# io-board-d-8.net
KiCad netlist of a schematic drawn in EAGLE
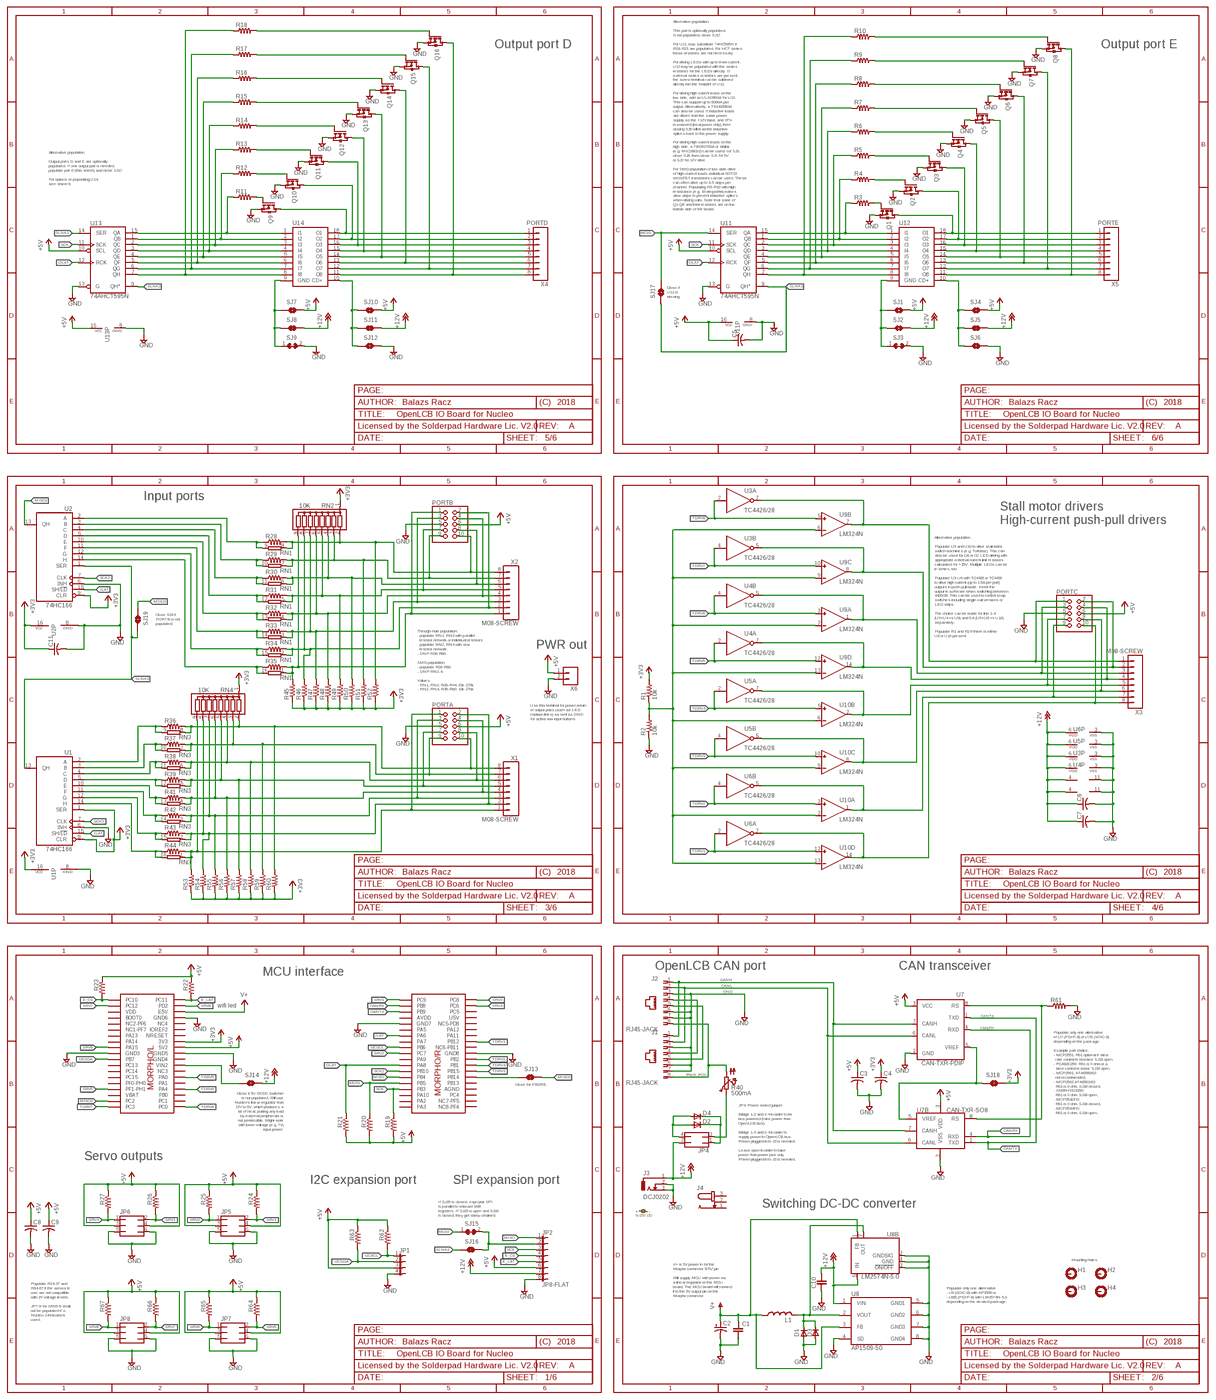
[diagram p0: schematic, sheet 1, overview]
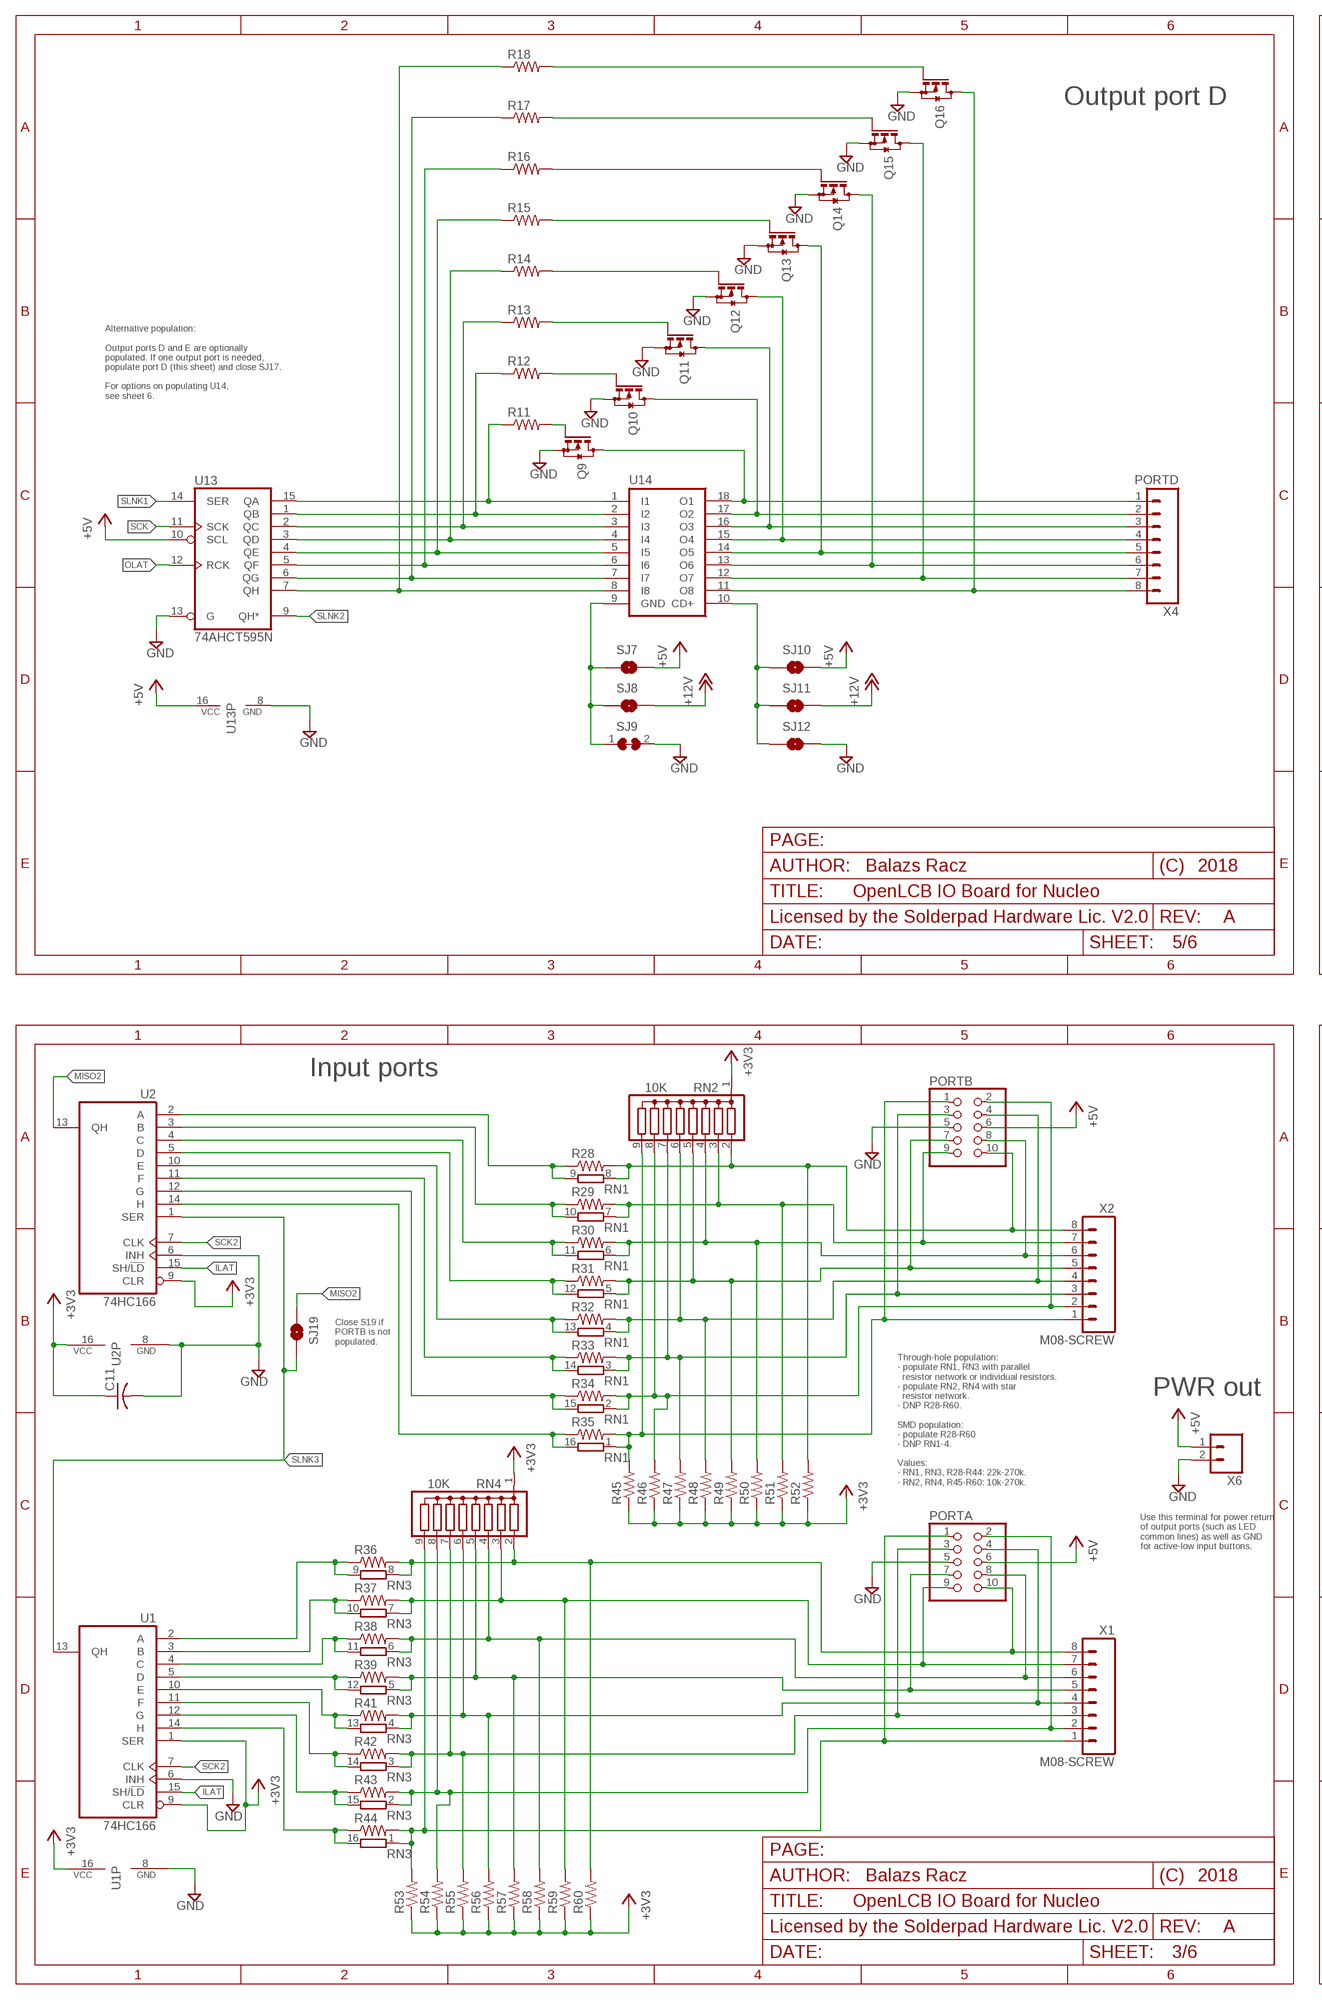
[diagram p1: schematic, sheet 1, part 1 of 4]
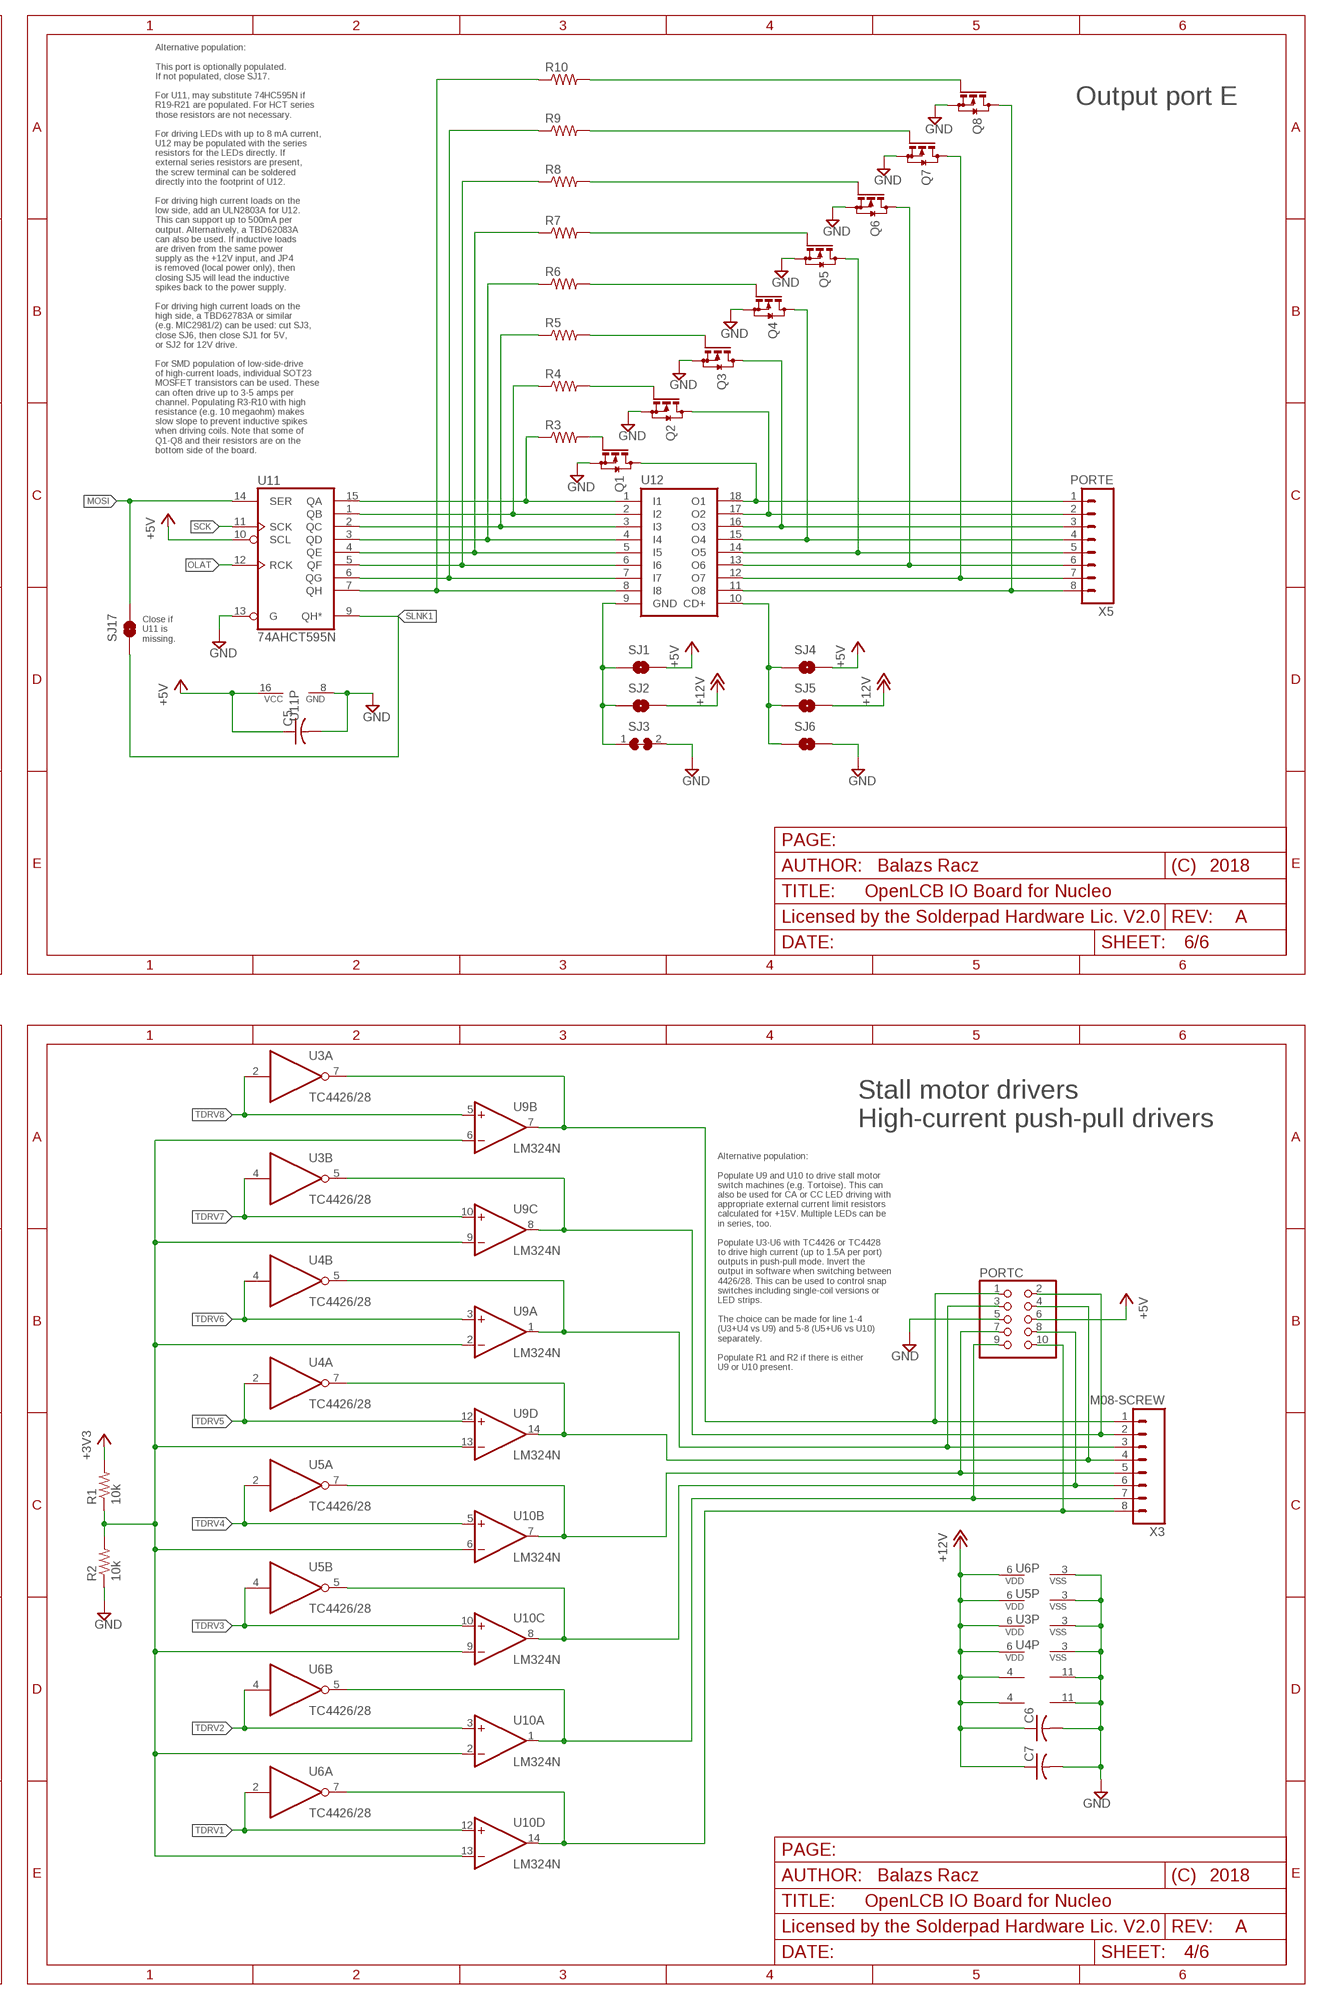
[diagram p2: schematic, sheet 1, part 2 of 4]
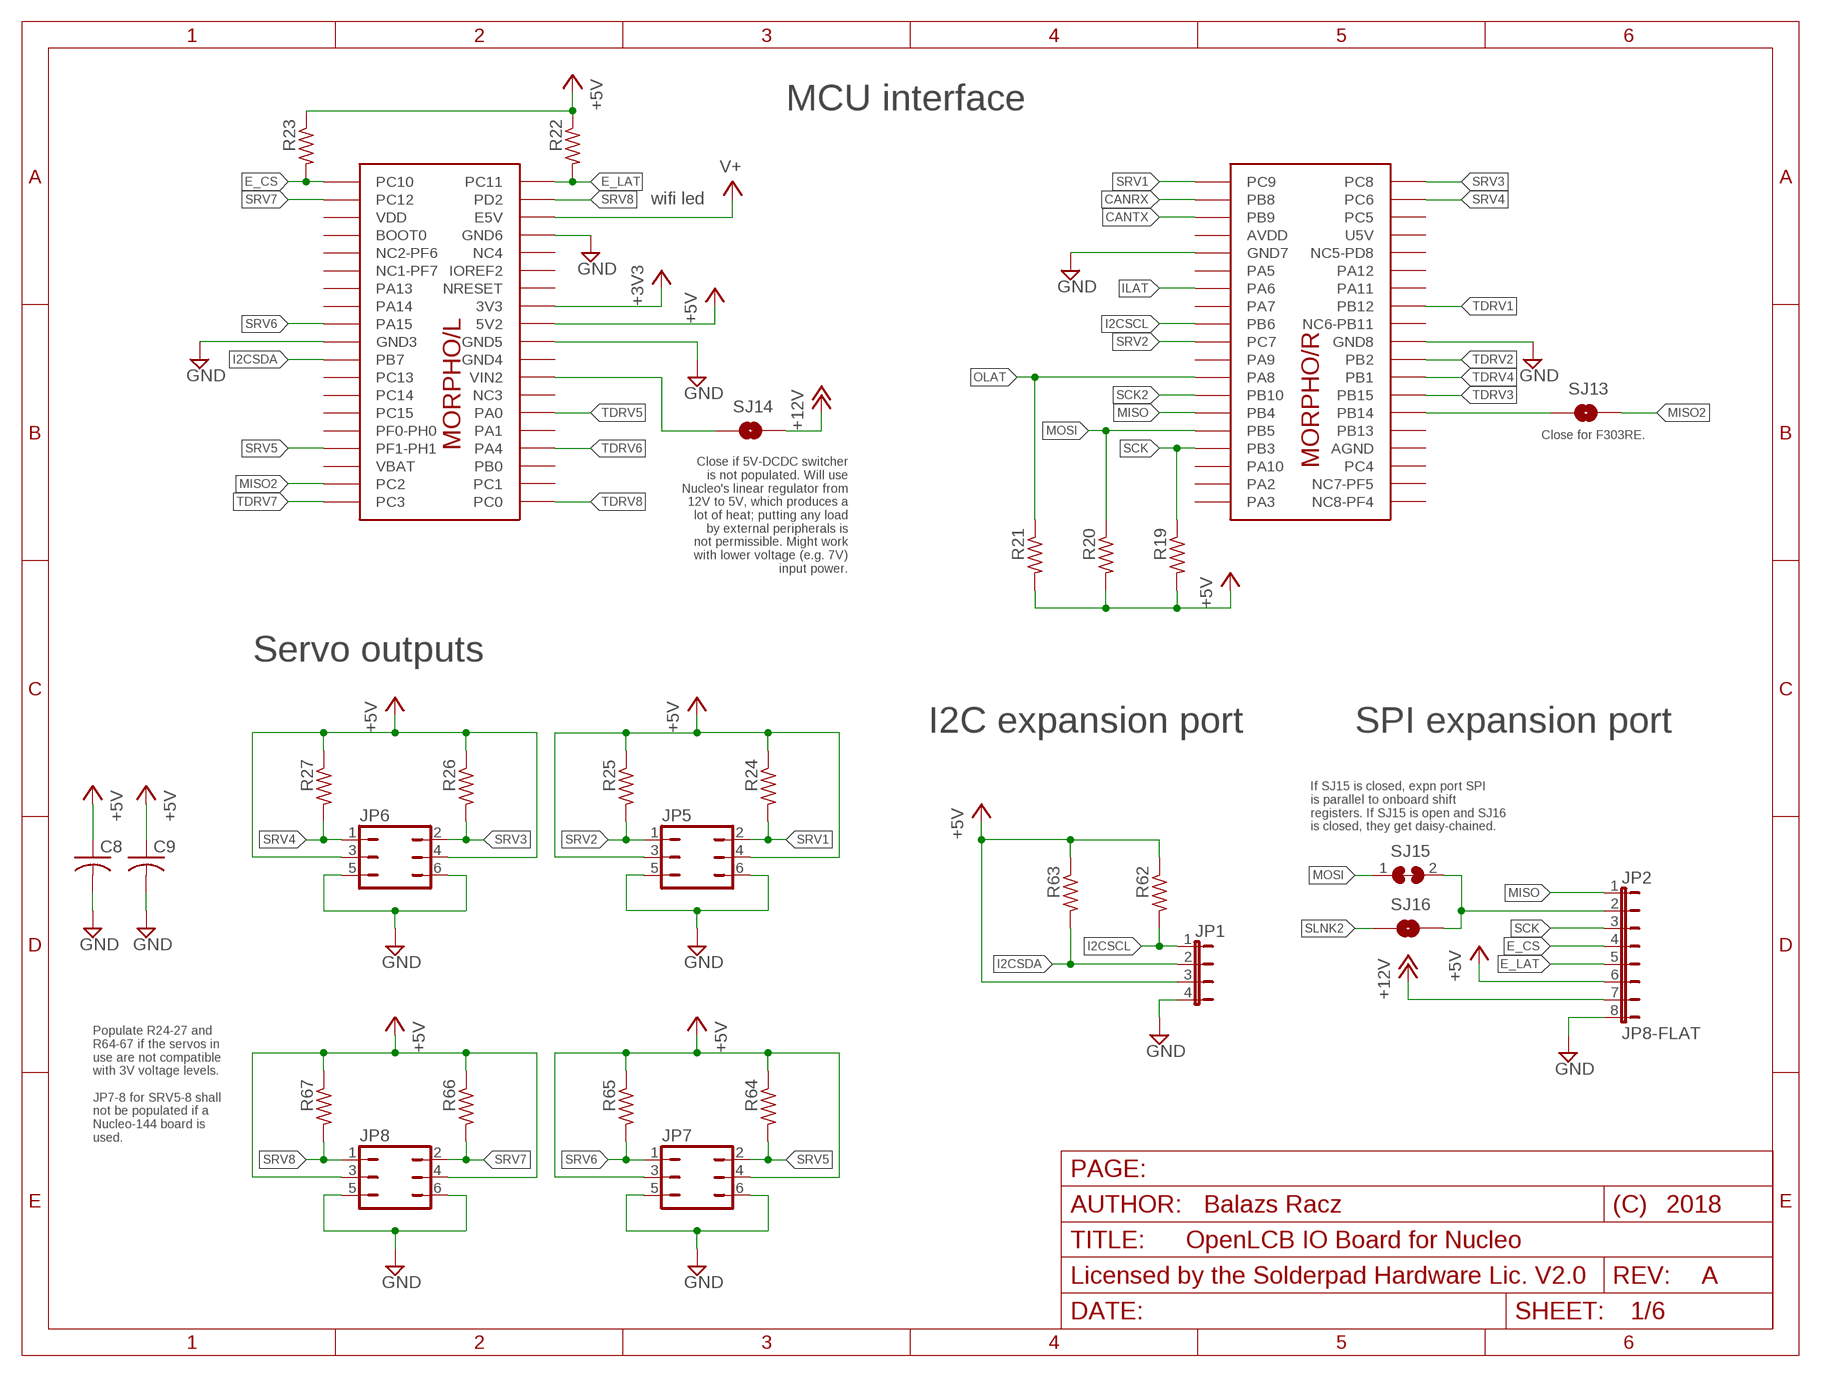
[diagram p3: schematic, sheet 1, part 3 of 4]
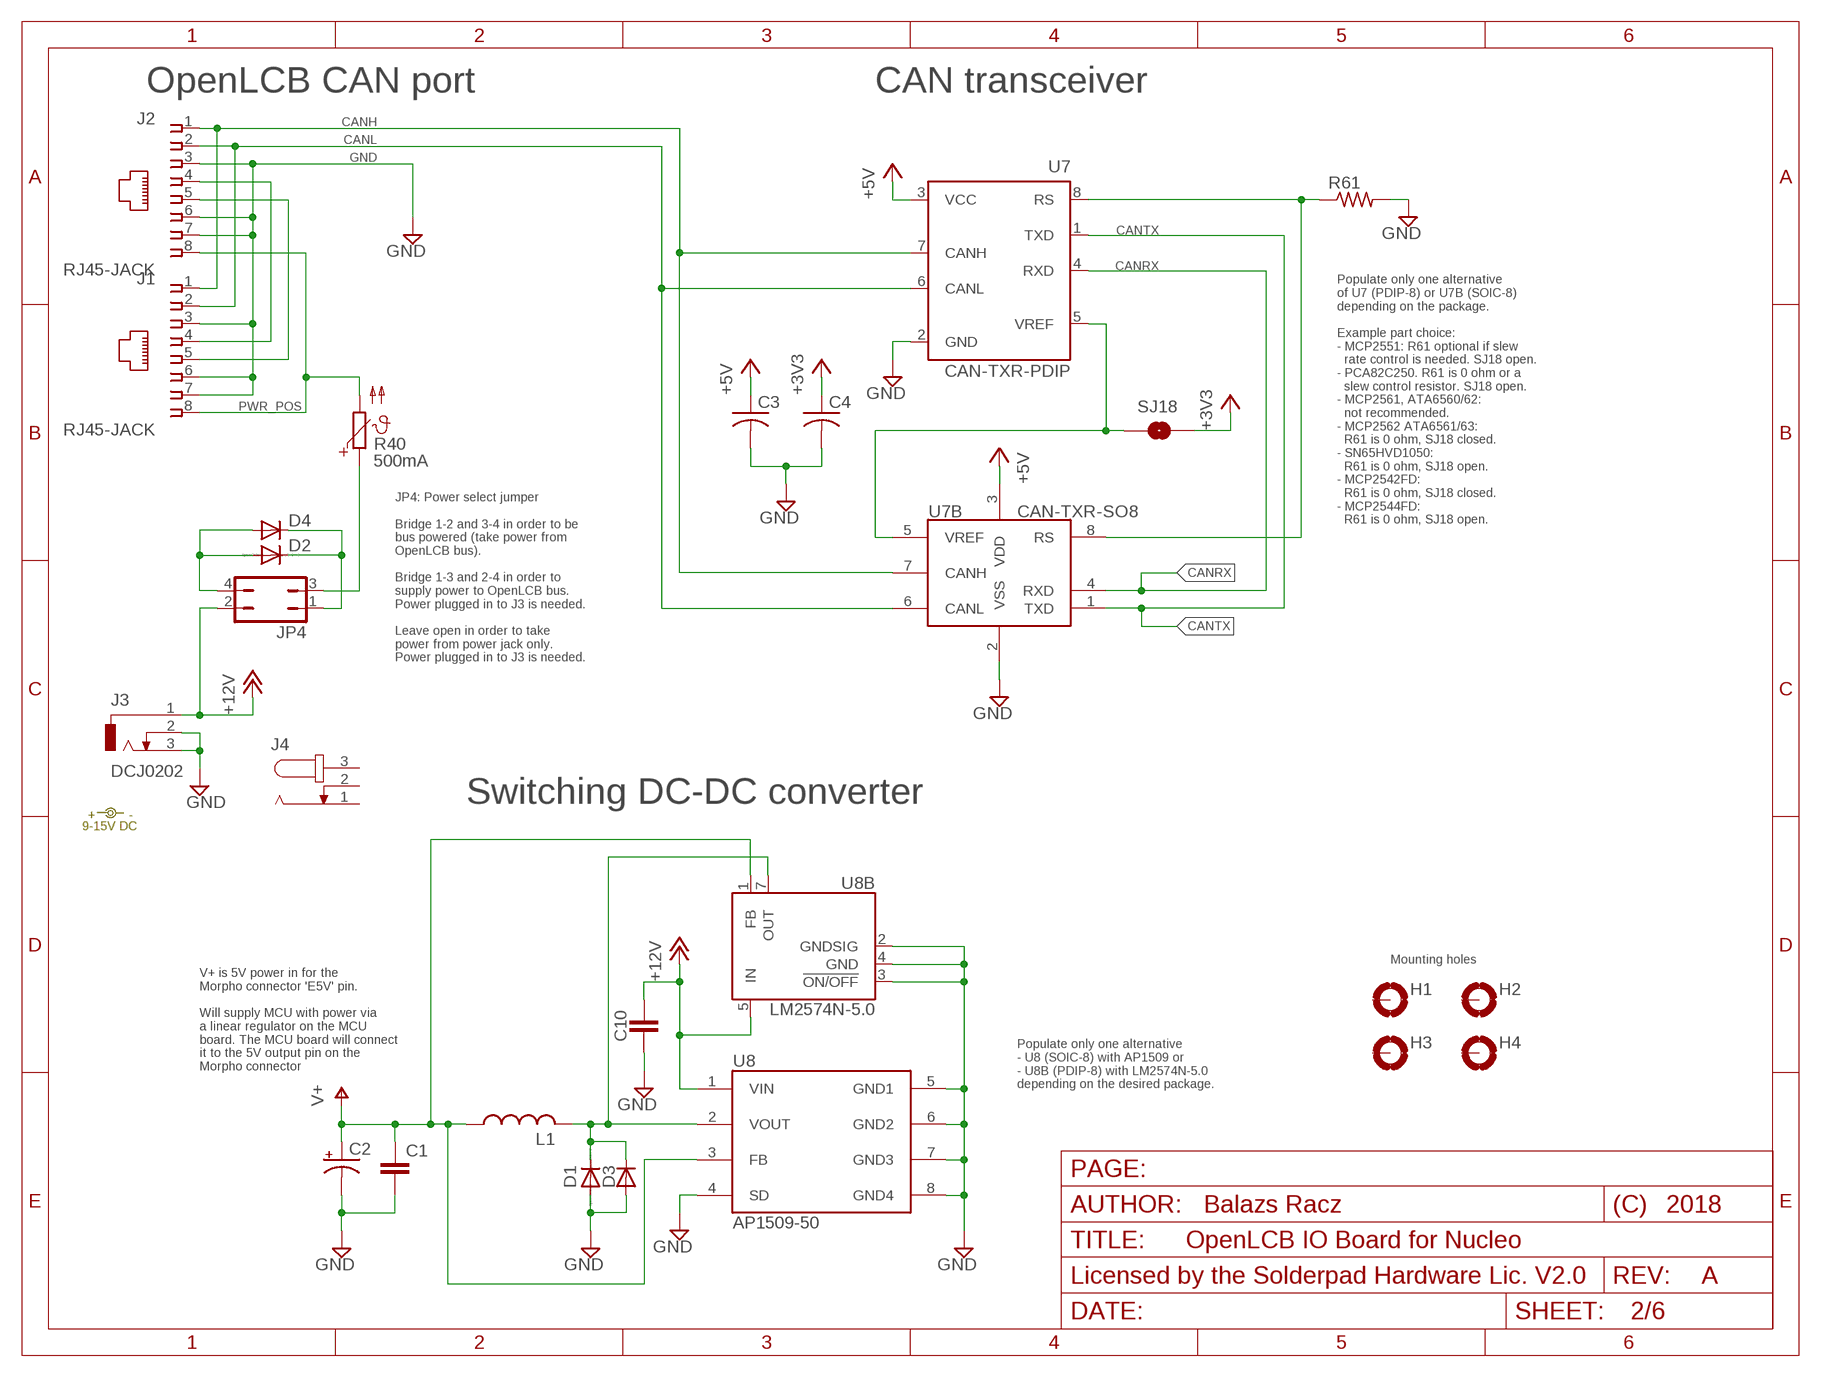
[diagram p4: schematic, sheet 1, part 4 of 4]

(export (version "E")
  (design (tool "Eeschema 10.0.6"))
  (components
    (comp (ref "+12V")
      (value "9-15V DC")
      (footprint "eagle-import:POWER_USAGE")
      (libsource (lib "eagle-import") (part "DOC-POWER_LABEL"))
    )
    (comp (ref "C1")
      (value "C-EUC1206")
      (footprint "eagle-import:C1206")
      (libsource (lib "eagle-import") (part "C-EUC1206"))
    )
    (comp (ref "C2")
      (value "CPOL-USE2.5-5")
      (footprint "eagle-import:E2,5-5")
      (libsource (lib "eagle-import") (part "CPOL-USE2.5-5"))
    )
    (comp (ref "C3")
      (value "C-USC0805")
      (footprint "eagle-import:C0805")
      (libsource (lib "eagle-import") (part "C-USC0805"))
    )
    (comp (ref "C4")
      (value "C-USC0805")
      (footprint "eagle-import:C0805")
      (libsource (lib "eagle-import") (part "C-USC0805"))
    )
    (comp (ref "C5")
      (value "C-USC0805")
      (footprint "eagle-import:C0805")
      (libsource (lib "eagle-import") (part "C-USC0805"))
    )
    (comp (ref "C6")
      (value "C-USC1206")
      (footprint "eagle-import:C1206")
      (libsource (lib "eagle-import") (part "C-USC1206"))
    )
    (comp (ref "C7")
      (value "C-USC1206")
      (footprint "eagle-import:C1206")
      (libsource (lib "eagle-import") (part "C-USC1206"))
    )
    (comp (ref "C8")
      (value "C-USC1206")
      (footprint "eagle-import:C1206")
      (libsource (lib "eagle-import") (part "C-USC1206"))
    )
    (comp (ref "C9")
      (value "C-USC1206")
      (footprint "eagle-import:C1206")
      (libsource (lib "eagle-import") (part "C-USC1206"))
    )
    (comp (ref "C10")
      (value "C-EUC1206")
      (footprint "eagle-import:C1206")
      (libsource (lib "eagle-import") (part "C-EUC1206"))
    )
    (comp (ref "C11")
      (value "C-USC0805")
      (footprint "eagle-import:C0805")
      (libsource (lib "eagle-import") (part "C-USC0805"))
    )
    (comp (ref "D1")
      (value "DIODE-DO41-7.6")
      (footprint "eagle-import:DO41-7.6")
      (libsource (lib "eagle-import") (part "DIODE-DO41-7.6"))
    )
    (comp (ref "D2")
      (value "DIODE-DO41-7.6")
      (footprint "eagle-import:DO41-7.6")
      (libsource (lib "eagle-import") (part "DIODE-DO41-7.6"))
    )
    (comp (ref "D3")
      (value "DIODEDO-214AA-NODOC")
      (footprint "eagle-import:DO214AA-NODOC")
      (libsource (lib "eagle-import") (part "DIODEDO-214AA-NODOC"))
    )
    (comp (ref "D4")
      (value "DIODEDO-214AA-NODOC")
      (footprint "eagle-import:DO214AA-NODOC")
      (libsource (lib "eagle-import") (part "DIODEDO-214AA-NODOC"))
    )
    (comp (ref "H1")
      (value "MOUNT-PAD-ROUND3.3")
      (footprint "eagle-import:3,3-PAD")
      (libsource (lib "eagle-import") (part "MOUNT-PAD-ROUND3.3"))
    )
    (comp (ref "H2")
      (value "MOUNT-PAD-ROUND3.3")
      (footprint "eagle-import:3,3-PAD")
      (libsource (lib "eagle-import") (part "MOUNT-PAD-ROUND3.3"))
    )
    (comp (ref "H3")
      (value "MOUNT-PAD-ROUND3.3")
      (footprint "eagle-import:3,3-PAD")
      (libsource (lib "eagle-import") (part "MOUNT-PAD-ROUND3.3"))
    )
    (comp (ref "H4")
      (value "MOUNT-PAD-ROUND3.3")
      (footprint "eagle-import:3,3-PAD")
      (libsource (lib "eagle-import") (part "MOUNT-PAD-ROUND3.3"))
    )
    (comp (ref "J1")
      (value "RJ45-JACK")
      (footprint "eagle-import:RJ45-PULSE-E5J88")
      (libsource (lib "eagle-import") (part "RJ45-JACKRJ45-PULSE-E5J00"))
    )
    (comp (ref "J2")
      (value "RJ45-JACK")
      (footprint "eagle-import:RJ45-PULSE-E5J88")
      (libsource (lib "eagle-import") (part "RJ45-JACKRJ45-PULSE-E5J00"))
    )
    (comp (ref "J3")
      (value "DCJ0202")
      (footprint "eagle-import:DCJ0202")
      (libsource (lib "eagle-import") (part "DCJ0202"))
    )
    (comp (ref "J4")
      (value "JACK-PLUG0")
      (footprint "eagle-import:SPC4077")
      (libsource (lib "eagle-import") (part "JACK-PLUG0"))
    )
    (comp (ref "JP1")
      (value "JP4-FLAT")
      (footprint "eagle-import:JP4F")
      (libsource (lib "eagle-import") (part "JP4-FLAT"))
    )
    (comp (ref "JP2")
      (value "JP8-FLAT")
      (footprint "eagle-import:JP8F")
      (libsource (lib "eagle-import") (part "JP8-FLAT"))
    )
    (comp (ref "JP4")
      (value "JP2Q")
      (footprint "eagle-import:JP2Q")
      (libsource (lib "eagle-import") (part "JP2Q"))
    )
    (comp (ref "JP5")
      (value "JP3Q")
      (footprint "eagle-import:JP3Q")
      (libsource (lib "eagle-import") (part "JP3Q"))
    )
    (comp (ref "JP6")
      (value "JP3Q")
      (footprint "eagle-import:JP3Q")
      (libsource (lib "eagle-import") (part "JP3Q"))
    )
    (comp (ref "JP7")
      (value "JP3Q")
      (footprint "eagle-import:JP3Q")
      (libsource (lib "eagle-import") (part "JP3Q"))
    )
    (comp (ref "JP8")
      (value "JP3Q")
      (footprint "eagle-import:JP3Q")
      (libsource (lib "eagle-import") (part "JP3Q"))
    )
    (comp (ref "L1")
      (value "L-US")
      (footprint "eagle-import:L5-8,5")
      (libsource (lib "eagle-import") (part "L-US"))
    )
    (comp (ref "PORTA")
      (value "PINHD-2X5CN")
      (footprint "eagle-import:CON10M")
      (libsource (lib "eagle-import") (part "PINHD-2X5CN"))
    )
    (comp (ref "PORTB")
      (value "PINHD-2X5CN")
      (footprint "eagle-import:CON10M")
      (libsource (lib "eagle-import") (part "PINHD-2X5CN"))
    )
    (comp (ref "PORTC")
      (value "PINHD-2X5CN")
      (footprint "eagle-import:CON10M")
      (libsource (lib "eagle-import") (part "PINHD-2X5CN"))
    )
    (comp (ref "Q1")
      (value "BSS123")
      (footprint "eagle-import:SOT23")
      (libsource (lib "eagle-import") (part "BSS123"))
    )
    (comp (ref "Q2")
      (value "BSS123")
      (footprint "eagle-import:SOT23")
      (libsource (lib "eagle-import") (part "BSS123"))
    )
    (comp (ref "Q3")
      (value "BSS123")
      (footprint "eagle-import:SOT23")
      (libsource (lib "eagle-import") (part "BSS123"))
    )
    (comp (ref "Q4")
      (value "BSS123")
      (footprint "eagle-import:SOT23")
      (libsource (lib "eagle-import") (part "BSS123"))
    )
    (comp (ref "Q5")
      (value "BSS123")
      (footprint "eagle-import:SOT23")
      (libsource (lib "eagle-import") (part "BSS123"))
    )
    (comp (ref "Q6")
      (value "BSS123")
      (footprint "eagle-import:SOT23")
      (libsource (lib "eagle-import") (part "BSS123"))
    )
    (comp (ref "Q7")
      (value "BSS123")
      (footprint "eagle-import:SOT23")
      (libsource (lib "eagle-import") (part "BSS123"))
    )
    (comp (ref "Q8")
      (value "BSS123")
      (footprint "eagle-import:SOT23")
      (libsource (lib "eagle-import") (part "BSS123"))
    )
    (comp (ref "Q9")
      (value "BSS123")
      (footprint "eagle-import:SOT23")
      (libsource (lib "eagle-import") (part "BSS123"))
    )
    (comp (ref "Q10")
      (value "BSS123")
      (footprint "eagle-import:SOT23")
      (libsource (lib "eagle-import") (part "BSS123"))
    )
    (comp (ref "Q11")
      (value "BSS123")
      (footprint "eagle-import:SOT23")
      (libsource (lib "eagle-import") (part "BSS123"))
    )
    (comp (ref "Q12")
      (value "BSS123")
      (footprint "eagle-import:SOT23")
      (libsource (lib "eagle-import") (part "BSS123"))
    )
    (comp (ref "Q13")
      (value "BSS123")
      (footprint "eagle-import:SOT23")
      (libsource (lib "eagle-import") (part "BSS123"))
    )
    (comp (ref "Q14")
      (value "BSS123")
      (footprint "eagle-import:SOT23")
      (libsource (lib "eagle-import") (part "BSS123"))
    )
    (comp (ref "Q15")
      (value "BSS123")
      (footprint "eagle-import:SOT23")
      (libsource (lib "eagle-import") (part "BSS123"))
    )
    (comp (ref "Q16")
      (value "BSS123")
      (footprint "eagle-import:SOT23")
      (libsource (lib "eagle-import") (part "BSS123"))
    )
    (comp (ref "R1")
      (value "10k")
      (footprint "eagle-import:R0805")
      (libsource (lib "eagle-import") (part "R-US_R0805"))
    )
    (comp (ref "R2")
      (value "10k")
      (footprint "eagle-import:R0805")
      (libsource (lib "eagle-import") (part "R-US_R0805"))
    )
    (comp (ref "R3")
      (value "R-US_R0603")
      (footprint "eagle-import:R0603")
      (libsource (lib "eagle-import") (part "R-US_R0603"))
    )
    (comp (ref "R4")
      (value "R-US_R0603")
      (footprint "eagle-import:R0603")
      (libsource (lib "eagle-import") (part "R-US_R0603"))
    )
    (comp (ref "R5")
      (value "R-US_R0603")
      (footprint "eagle-import:R0603")
      (libsource (lib "eagle-import") (part "R-US_R0603"))
    )
    (comp (ref "R6")
      (value "R-US_R0603")
      (footprint "eagle-import:R0603")
      (libsource (lib "eagle-import") (part "R-US_R0603"))
    )
    (comp (ref "R7")
      (value "R-US_R0603")
      (footprint "eagle-import:R0603")
      (libsource (lib "eagle-import") (part "R-US_R0603"))
    )
    (comp (ref "R8")
      (value "R-US_R0603")
      (footprint "eagle-import:R0603")
      (libsource (lib "eagle-import") (part "R-US_R0603"))
    )
    (comp (ref "R9")
      (value "R-US_R0603")
      (footprint "eagle-import:R0603")
      (libsource (lib "eagle-import") (part "R-US_R0603"))
    )
    (comp (ref "R10")
      (value "R-US_R0603")
      (footprint "eagle-import:R0603")
      (libsource (lib "eagle-import") (part "R-US_R0603"))
    )
    (comp (ref "R11")
      (value "R-US_R0603")
      (footprint "eagle-import:R0603")
      (libsource (lib "eagle-import") (part "R-US_R0603"))
    )
    (comp (ref "R12")
      (value "R-US_R0603")
      (footprint "eagle-import:R0603")
      (libsource (lib "eagle-import") (part "R-US_R0603"))
    )
    (comp (ref "R13")
      (value "R-US_R0603")
      (footprint "eagle-import:R0603")
      (libsource (lib "eagle-import") (part "R-US_R0603"))
    )
    (comp (ref "R14")
      (value "R-US_R0603")
      (footprint "eagle-import:R0603")
      (libsource (lib "eagle-import") (part "R-US_R0603"))
    )
    (comp (ref "R15")
      (value "R-US_R0603")
      (footprint "eagle-import:R0603")
      (libsource (lib "eagle-import") (part "R-US_R0603"))
    )
    (comp (ref "R16")
      (value "R-US_R0603")
      (footprint "eagle-import:R0603")
      (libsource (lib "eagle-import") (part "R-US_R0603"))
    )
    (comp (ref "R17")
      (value "R-US_R0603")
      (footprint "eagle-import:R0603")
      (libsource (lib "eagle-import") (part "R-US_R0603"))
    )
    (comp (ref "R18")
      (value "R-US_R0603")
      (footprint "eagle-import:R0603")
      (libsource (lib "eagle-import") (part "R-US_R0603"))
    )
    (comp (ref "R19")
      (value "R-US_R0805")
      (footprint "eagle-import:R0805")
      (libsource (lib "eagle-import") (part "rcl_334_R-US_R0805"))
    )
    (comp (ref "R20")
      (value "R-US_R0805")
      (footprint "eagle-import:R0805")
      (libsource (lib "eagle-import") (part "rcl_334_R-US_R0805"))
    )
    (comp (ref "R21")
      (value "R-US_R0805")
      (footprint "eagle-import:R0805")
      (libsource (lib "eagle-import") (part "rcl_334_R-US_R0805"))
    )
    (comp (ref "R22")
      (value "R-US_R0805")
      (footprint "eagle-import:R0805")
      (libsource (lib "eagle-import") (part "rcl_334_R-US_R0805"))
    )
    (comp (ref "R23")
      (value "R-US_R0805")
      (footprint "eagle-import:R0805")
      (libsource (lib "eagle-import") (part "rcl_334_R-US_R0805"))
    )
    (comp (ref "R24")
      (value "R-US_R0805")
      (footprint "eagle-import:R0805")
      (libsource (lib "eagle-import") (part "rcl_334_R-US_R0805"))
    )
    (comp (ref "R25")
      (value "R-US_R0805")
      (footprint "eagle-import:R0805")
      (libsource (lib "eagle-import") (part "rcl_334_R-US_R0805"))
    )
    (comp (ref "R26")
      (value "R-US_R0805")
      (footprint "eagle-import:R0805")
      (libsource (lib "eagle-import") (part "rcl_334_R-US_R0805"))
    )
    (comp (ref "R27")
      (value "R-US_R0805")
      (footprint "eagle-import:R0805")
      (libsource (lib "eagle-import") (part "rcl_334_R-US_R0805"))
    )
    (comp (ref "R28")
      (value "R-US_R0603")
      (footprint "eagle-import:R0603")
      (libsource (lib "eagle-import") (part "rcl_334_R-US_R0603"))
    )
    (comp (ref "R29")
      (value "R-US_R0603")
      (footprint "eagle-import:R0603")
      (libsource (lib "eagle-import") (part "rcl_334_R-US_R0603"))
    )
    (comp (ref "R30")
      (value "R-US_R0603")
      (footprint "eagle-import:R0603")
      (libsource (lib "eagle-import") (part "rcl_334_R-US_R0603"))
    )
    (comp (ref "R31")
      (value "R-US_R0603")
      (footprint "eagle-import:R0603")
      (libsource (lib "eagle-import") (part "rcl_334_R-US_R0603"))
    )
    (comp (ref "R32")
      (value "R-US_R0603")
      (footprint "eagle-import:R0603")
      (libsource (lib "eagle-import") (part "rcl_334_R-US_R0603"))
    )
    (comp (ref "R33")
      (value "R-US_R0603")
      (footprint "eagle-import:R0603")
      (libsource (lib "eagle-import") (part "rcl_334_R-US_R0603"))
    )
    (comp (ref "R34")
      (value "R-US_R0603")
      (footprint "eagle-import:R0603")
      (libsource (lib "eagle-import") (part "rcl_334_R-US_R0603"))
    )
    (comp (ref "R35")
      (value "R-US_R0603")
      (footprint "eagle-import:R0603")
      (libsource (lib "eagle-import") (part "rcl_334_R-US_R0603"))
    )
    (comp (ref "R36")
      (value "R-US_R0603")
      (footprint "eagle-import:R0603")
      (libsource (lib "eagle-import") (part "rcl_334_R-US_R0603"))
    )
    (comp (ref "R37")
      (value "R-US_R0603")
      (footprint "eagle-import:R0603")
      (libsource (lib "eagle-import") (part "rcl_334_R-US_R0603"))
    )
    (comp (ref "R38")
      (value "R-US_R0603")
      (footprint "eagle-import:R0603")
      (libsource (lib "eagle-import") (part "rcl_334_R-US_R0603"))
    )
    (comp (ref "R39")
      (value "R-US_R0603")
      (footprint "eagle-import:R0603")
      (libsource (lib "eagle-import") (part "rcl_334_R-US_R0603"))
    )
    (comp (ref "R40")
      (value "500mA")
      (footprint "eagle-import:PTC1812")
      (libsource (lib "eagle-import") (part "PTC_1812"))
    )
    (comp (ref "R41")
      (value "R-US_R0603")
      (footprint "eagle-import:R0603")
      (libsource (lib "eagle-import") (part "rcl_334_R-US_R0603"))
    )
    (comp (ref "R42")
      (value "R-US_R0603")
      (footprint "eagle-import:R0603")
      (libsource (lib "eagle-import") (part "rcl_334_R-US_R0603"))
    )
    (comp (ref "R43")
      (value "R-US_R0603")
      (footprint "eagle-import:R0603")
      (libsource (lib "eagle-import") (part "rcl_334_R-US_R0603"))
    )
    (comp (ref "R44")
      (value "R-US_R0603")
      (footprint "eagle-import:R0603")
      (libsource (lib "eagle-import") (part "rcl_334_R-US_R0603"))
    )
    (comp (ref "R45")
      (value "R-US")
      (footprint "eagle-import:R0603")
      (libsource (lib "eagle-import") (part "R-US"))
    )
    (comp (ref "R46")
      (value "R-US")
      (footprint "eagle-import:R0603")
      (libsource (lib "eagle-import") (part "R-US"))
    )
    (comp (ref "R47")
      (value "R-US")
      (footprint "eagle-import:R0603")
      (libsource (lib "eagle-import") (part "R-US"))
    )
    (comp (ref "R48")
      (value "R-US")
      (footprint "eagle-import:R0603")
      (libsource (lib "eagle-import") (part "R-US"))
    )
    (comp (ref "R49")
      (value "R-US")
      (footprint "eagle-import:R0603")
      (libsource (lib "eagle-import") (part "R-US"))
    )
    (comp (ref "R50")
      (value "R-US")
      (footprint "eagle-import:R0603")
      (libsource (lib "eagle-import") (part "R-US"))
    )
    (comp (ref "R51")
      (value "R-US")
      (footprint "eagle-import:R0603")
      (libsource (lib "eagle-import") (part "R-US"))
    )
    (comp (ref "R52")
      (value "R-US")
      (footprint "eagle-import:R0603")
      (libsource (lib "eagle-import") (part "R-US"))
    )
    (comp (ref "R53")
      (value "R-US")
      (footprint "eagle-import:R0603")
      (libsource (lib "eagle-import") (part "R-US"))
    )
    (comp (ref "R54")
      (value "R-US")
      (footprint "eagle-import:R0603")
      (libsource (lib "eagle-import") (part "R-US"))
    )
    (comp (ref "R55")
      (value "R-US")
      (footprint "eagle-import:R0603")
      (libsource (lib "eagle-import") (part "R-US"))
    )
    (comp (ref "R56")
      (value "R-US")
      (footprint "eagle-import:R0603")
      (libsource (lib "eagle-import") (part "R-US"))
    )
    (comp (ref "R57")
      (value "R-US")
      (footprint "eagle-import:R0603")
      (libsource (lib "eagle-import") (part "R-US"))
    )
    (comp (ref "R58")
      (value "R-US")
      (footprint "eagle-import:R0603")
      (libsource (lib "eagle-import") (part "R-US"))
    )
    (comp (ref "R59")
      (value "R-US")
      (footprint "eagle-import:R0603")
      (libsource (lib "eagle-import") (part "R-US"))
    )
    (comp (ref "R60")
      (value "R-US")
      (footprint "eagle-import:R0603")
      (libsource (lib "eagle-import") (part "R-US"))
    )
    (comp (ref "R61")
      (value "R-US_R0805")
      (footprint "eagle-import:R0805")
      (libsource (lib "eagle-import") (part "rcl_334_R-US_R0805"))
    )
    (comp (ref "R62")
      (value "R-US_R0805")
      (footprint "eagle-import:R0805")
      (libsource (lib "eagle-import") (part "rcl_334_R-US_R0805"))
    )
    (comp (ref "R63")
      (value "R-US_R0805")
      (footprint "eagle-import:R0805")
      (libsource (lib "eagle-import") (part "rcl_334_R-US_R0805"))
    )
    (comp (ref "R64")
      (value "R-US_R0805")
      (footprint "eagle-import:R0805")
      (libsource (lib "eagle-import") (part "rcl_334_R-US_R0805"))
    )
    (comp (ref "R65")
      (value "R-US_R0805")
      (footprint "eagle-import:R0805")
      (libsource (lib "eagle-import") (part "rcl_334_R-US_R0805"))
    )
    (comp (ref "R66")
      (value "R-US_R0805")
      (footprint "eagle-import:R0805")
      (libsource (lib "eagle-import") (part "rcl_334_R-US_R0805"))
    )
    (comp (ref "R67")
      (value "R-US_R0805")
      (footprint "eagle-import:R0805")
      (libsource (lib "eagle-import") (part "rcl_334_R-US_R0805"))
    )
    (comp (ref "RN1")
      (value "8R-P")
      (footprint "eagle-import:DIL16")
      (libsource (lib "eagle-import") (part "8R-P"))
    )
    (comp (ref "RN2")
      (value "10K")
      (footprint "eagle-import:SIL9")
      (libsource (lib "eagle-import") (part "G08R"))
    )
    (comp (ref "RN3")
      (value "8R-P")
      (footprint "eagle-import:DIL16")
      (libsource (lib "eagle-import") (part "8R-P"))
    )
    (comp (ref "RN4")
      (value "10K")
      (footprint "eagle-import:SIL9")
      (libsource (lib "eagle-import") (part "G08R"))
    )
    (comp (ref "SJ1")
      (value "SJRND2")
      (footprint "eagle-import:SJ_RND2")
      (libsource (lib "eagle-import") (part "SJRND2"))
    )
    (comp (ref "SJ2")
      (value "SJRND2")
      (footprint "eagle-import:SJ_RND2")
      (libsource (lib "eagle-import") (part "SJRND2"))
    )
    (comp (ref "SJ3")
      (value "SJ-C")
      (footprint "eagle-import:SJW-C")
      (libsource (lib "eagle-import") (part "SJ-C"))
    )
    (comp (ref "SJ4")
      (value "SJRND2")
      (footprint "eagle-import:SJ_RND2")
      (libsource (lib "eagle-import") (part "SJRND2"))
    )
    (comp (ref "SJ5")
      (value "SJRND2")
      (footprint "eagle-import:SJ_RND2")
      (libsource (lib "eagle-import") (part "SJRND2"))
    )
    (comp (ref "SJ6")
      (value "SJRND2")
      (footprint "eagle-import:SJ_RND2")
      (libsource (lib "eagle-import") (part "SJRND2"))
    )
    (comp (ref "SJ7")
      (value "SJRND2")
      (footprint "eagle-import:SJ_RND2")
      (libsource (lib "eagle-import") (part "SJRND2"))
    )
    (comp (ref "SJ8")
      (value "SJRND2")
      (footprint "eagle-import:SJ_RND2")
      (libsource (lib "eagle-import") (part "SJRND2"))
    )
    (comp (ref "SJ9")
      (value "SJ-C")
      (footprint "eagle-import:SJW-C")
      (libsource (lib "eagle-import") (part "SJ-C"))
    )
    (comp (ref "SJ10")
      (value "SJRND2")
      (footprint "eagle-import:SJ_RND2")
      (libsource (lib "eagle-import") (part "SJRND2"))
    )
    (comp (ref "SJ11")
      (value "SJRND2")
      (footprint "eagle-import:SJ_RND2")
      (libsource (lib "eagle-import") (part "SJRND2"))
    )
    (comp (ref "SJ12")
      (value "SJRND2")
      (footprint "eagle-import:SJ_RND2")
      (libsource (lib "eagle-import") (part "SJRND2"))
    )
    (comp (ref "SJ13")
      (value "SJRND2")
      (footprint "eagle-import:SJ_RND2")
      (libsource (lib "eagle-import") (part "SJRND2"))
    )
    (comp (ref "SJ14")
      (value "SJRND2")
      (footprint "eagle-import:SJ_RND2")
      (libsource (lib "eagle-import") (part "SJRND2"))
    )
    (comp (ref "SJ15")
      (value "SJ-C")
      (footprint "eagle-import:SJW-C")
      (libsource (lib "eagle-import") (part "SJ-C"))
    )
    (comp (ref "SJ16")
      (value "SJRND2")
      (footprint "eagle-import:SJ_RND2")
      (libsource (lib "eagle-import") (part "SJRND2"))
    )
    (comp (ref "SJ17")
      (value "SJRND2")
      (footprint "eagle-import:SJ_RND2")
      (libsource (lib "eagle-import") (part "SJRND2"))
    )
    (comp (ref "SJ18")
      (value "SJRND2")
      (footprint "eagle-import:SJ_RND2")
      (libsource (lib "eagle-import") (part "SJRND2"))
    )
    (comp (ref "SJ19")
      (value "SJRND2")
      (footprint "eagle-import:SJ_RND2")
      (libsource (lib "eagle-import") (part "SJRND2"))
    )
    (comp (ref "U$1")
      (value "NUCLEO_64_GENERIC")
      (footprint "eagle-import:NUCLEO_BRD_BASE64")
      (libsource (lib "eagle-import") (part "NUCLEO_64_GENERIC"))
    )
    (comp (ref "U1")
      (value "74HC166")
      (footprint "eagle-import:DIL16")
      (libsource (lib "eagle-import") (part "74166N"))
    )
    (comp (ref "U2")
      (value "74HC166")
      (footprint "eagle-import:DIL16")
      (libsource (lib "eagle-import") (part "74166N"))
    )
    (comp (ref "U3")
      (value "TC4426/28")
      (footprint "eagle-import:DIL08-LONG")
      (libsource (lib "eagle-import") (part "TC4426APDIP"))
    )
    (comp (ref "U4")
      (value "TC4426/28")
      (footprint "eagle-import:DIL08-LONG")
      (libsource (lib "eagle-import") (part "TC4426APDIP"))
    )
    (comp (ref "U5")
      (value "TC4426/28")
      (footprint "eagle-import:DIL08-LONG")
      (libsource (lib "eagle-import") (part "TC4426APDIP"))
    )
    (comp (ref "U6")
      (value "TC4426/28")
      (footprint "eagle-import:DIL08-LONG")
      (libsource (lib "eagle-import") (part "TC4426APDIP"))
    )
    (comp (ref "U7")
      (value "CAN-TXR-PDIP")
      (footprint "eagle-import:DIL08")
      (libsource (lib "eagle-import") (part "PCA82C250"))
    )
    (comp (ref "U7B")
      (value "CAN-TXR-SO8")
      (footprint "eagle-import:SO-08")
      (libsource (lib "eagle-import") (part "MCP2551-SN"))
    )
    (comp (ref "U8")
      (value "AP1509-50")
      (footprint "eagle-import:SO-08")
      (libsource (lib "eagle-import") (part "AP1509"))
    )
    (comp (ref "U8B")
      (value "LM2574N-5.0")
      (footprint "eagle-import:DIL08")
      (libsource (lib "eagle-import") (part "LM2574?-N5.0"))
    )
    (comp (ref "U9")
      (value "LM324N")
      (footprint "eagle-import:DIL14")
      (libsource (lib "eagle-import") (part "LM324N"))
    )
    (comp (ref "U10")
      (value "LM324N")
      (footprint "eagle-import:DIL14")
      (libsource (lib "eagle-import") (part "LM324N"))
    )
    (comp (ref "U11")
      (value "74AHCT595N")
      (footprint "eagle-import:DIL16")
      (libsource (lib "eagle-import") (part "74595NHCT"))
    )
    (comp (ref "U12")
      (value "ULN2803A")
      (footprint "eagle-import:DIL18-THIN")
      (libsource (lib "eagle-import") (part "ULN2803A"))
    )
    (comp (ref "U13")
      (value "74AHCT595N")
      (footprint "eagle-import:DIL16")
      (libsource (lib "eagle-import") (part "74595NHCT"))
    )
    (comp (ref "U14")
      (value "ULN2803A")
      (footprint "eagle-import:DIL18-THIN")
      (libsource (lib "eagle-import") (part "ULN2803A"))
    )
    (comp (ref "X1")
      (value "M08-SCREW")
      (footprint "eagle-import:1X08_TERMINAL")
      (libsource (lib "eagle-import") (part "M08-SCREW"))
    )
    (comp (ref "X2")
      (value "M08-SCREW")
      (footprint "eagle-import:1X08_TERMINAL")
      (libsource (lib "eagle-import") (part "M08-SCREW"))
    )
    (comp (ref "X3")
      (value "M08-SCREW")
      (footprint "eagle-import:1X08_TERMINAL")
      (libsource (lib "eagle-import") (part "M08-SCREW"))
    )
    (comp (ref "X4")
      (value "PORTD")
      (footprint "eagle-import:1X08_TERMINAL")
      (libsource (lib "eagle-import") (part "M08-SCREW"))
    )
    (comp (ref "X5")
      (value "PORTE")
      (footprint "eagle-import:1X08_TERMINAL")
      (libsource (lib "eagle-import") (part "M08-SCREW"))
    )
    (comp (ref "X6")
      (value "CONNECTOR-M023.5MM-LOCK")
      (footprint "eagle-import:SCREWTERMINAL-3.5MM-2_LOCK")
      (libsource (lib "eagle-import") (part "CONNECTOR-M023.5MM-LOCK"))
    )
  )
  (nets
    (net (code "1") (name "+3V3") (class "Default")
      (node (ref "C11") (pin "1") (pinfunction "1_1") (pintype "passive"))
      (node (ref "C4") (pin "1") (pinfunction "1_1") (pintype "passive"))
      (node (ref "R1") (pin "2") (pinfunction "2_2") (pintype "passive"))
      (node (ref "R45") (pin "1") (pinfunction "1_1") (pintype "passive"))
      (node (ref "R46") (pin "1") (pinfunction "1_1") (pintype "passive"))
      (node (ref "R47") (pin "1") (pinfunction "1_1") (pintype "passive"))
      (node (ref "R48") (pin "1") (pinfunction "1_1") (pintype "passive"))
      (node (ref "R49") (pin "1") (pinfunction "1_1") (pintype "passive"))
      (node (ref "R50") (pin "1") (pinfunction "1_1") (pintype "passive"))
      (node (ref "R51") (pin "1") (pinfunction "1_1") (pintype "passive"))
      (node (ref "R52") (pin "1") (pinfunction "1_1") (pintype "passive"))
      (node (ref "R53") (pin "1") (pinfunction "1_1") (pintype "passive"))
      (node (ref "R54") (pin "1") (pinfunction "1_1") (pintype "passive"))
      (node (ref "R55") (pin "1") (pinfunction "1_1") (pintype "passive"))
      (node (ref "R56") (pin "1") (pinfunction "1_1") (pintype "passive"))
      (node (ref "R57") (pin "1") (pinfunction "1_1") (pintype "passive"))
      (node (ref "R58") (pin "1") (pinfunction "1_1") (pintype "passive"))
      (node (ref "R59") (pin "1") (pinfunction "1_1") (pintype "passive"))
      (node (ref "R60") (pin "1") (pinfunction "1_1") (pintype "passive"))
      (node (ref "RN2") (pin "1") (pinfunction "1_1") (pintype "passive"))
      (node (ref "RN4") (pin "1") (pinfunction "1_1") (pintype "passive"))
      (node (ref "SJ18") (pin "P$1") (pinfunction "1_P$1") (pintype "passive"))
      (node (ref "U$1") (pin "3V3") (pinfunction "3V3_3V3") (pintype "power_in"))
      (node (ref "U1") (pin "1") (pinfunction "SER_1") (pintype "input"))
      (node (ref "U1") (pin "16") (pinfunction "VCC_16") (pintype "power_in"))
      (node (ref "U1") (pin "9") (pinfunction "CLR_9") (pintype "input"))
      (node (ref "U2") (pin "16") (pinfunction "VCC_16") (pintype "power_in"))
      (node (ref "U2") (pin "9") (pinfunction "CLR_9") (pintype "input"))
    )
    (net (code "2") (name "+5V") (class "Default")
      (node (ref "C3") (pin "1") (pinfunction "1_1") (pintype "passive"))
      (node (ref "C5") (pin "1") (pinfunction "1_1") (pintype "passive"))
      (node (ref "C8") (pin "1") (pinfunction "1_1") (pintype "passive"))
      (node (ref "C9") (pin "1") (pinfunction "1_1") (pintype "passive"))
      (node (ref "JP1") (pin "3") (pinfunction "3_3") (pintype "passive"))
      (node (ref "JP2") (pin "6") (pinfunction "6_6") (pintype "passive"))
      (node (ref "JP5") (pin "3") (pinfunction "3_3") (pintype "passive"))
      (node (ref "JP5") (pin "4") (pinfunction "4_4") (pintype "passive"))
      (node (ref "JP6") (pin "3") (pinfunction "3_3") (pintype "passive"))
      (node (ref "JP6") (pin "4") (pinfunction "4_4") (pintype "passive"))
      (node (ref "JP7") (pin "3") (pinfunction "3_3") (pintype "passive"))
      (node (ref "JP7") (pin "4") (pinfunction "4_4") (pintype "passive"))
      (node (ref "JP8") (pin "3") (pinfunction "3_3") (pintype "passive"))
      (node (ref "JP8") (pin "4") (pinfunction "4_4") (pintype "passive"))
      (node (ref "PORTA") (pin "6") (pinfunction "6_6") (pintype "passive"))
      (node (ref "PORTB") (pin "6") (pinfunction "6_6") (pintype "passive"))
      (node (ref "PORTC") (pin "6") (pinfunction "6_6") (pintype "passive"))
      (node (ref "R19") (pin "2") (pinfunction "2_2") (pintype "passive"))
      (node (ref "R20") (pin "2") (pinfunction "2_2") (pintype "passive"))
      (node (ref "R21") (pin "2") (pinfunction "2_2") (pintype "passive"))
      (node (ref "R22") (pin "1") (pinfunction "1_1") (pintype "passive"))
      (node (ref "R23") (pin "1") (pinfunction "1_1") (pintype "passive"))
      (node (ref "R24") (pin "1") (pinfunction "1_1") (pintype "passive"))
      (node (ref "R25") (pin "1") (pinfunction "1_1") (pintype "passive"))
      (node (ref "R26") (pin "1") (pinfunction "1_1") (pintype "passive"))
      (node (ref "R27") (pin "1") (pinfunction "1_1") (pintype "passive"))
      (node (ref "R62") (pin "1") (pinfunction "1_1") (pintype "passive"))
      (node (ref "R63") (pin "1") (pinfunction "1_1") (pintype "passive"))
      (node (ref "R64") (pin "1") (pinfunction "1_1") (pintype "passive"))
      (node (ref "R65") (pin "1") (pinfunction "1_1") (pintype "passive"))
      (node (ref "R66") (pin "1") (pinfunction "1_1") (pintype "passive"))
      (node (ref "R67") (pin "1") (pinfunction "1_1") (pintype "passive"))
      (node (ref "SJ1") (pin "P$2") (pinfunction "2_P$2") (pintype "passive"))
      (node (ref "SJ10") (pin "P$2") (pinfunction "2_P$2") (pintype "passive"))
      (node (ref "SJ4") (pin "P$2") (pinfunction "2_P$2") (pintype "passive"))
      (node (ref "SJ7") (pin "P$2") (pinfunction "2_P$2") (pintype "passive"))
      (node (ref "U$1") (pin "5V2") (pinfunction "5V2_5V2") (pintype "power_in"))
      (node (ref "U11") (pin "10") (pinfunction "SCL_10") (pintype "input"))
      (node (ref "U11") (pin "16") (pinfunction "VCC_16") (pintype "power_in"))
      (node (ref "U13") (pin "10") (pinfunction "SCL_10") (pintype "input"))
      (node (ref "U13") (pin "16") (pinfunction "VCC_16") (pintype "power_in"))
      (node (ref "U7") (pin "3") (pinfunction "VCC_3") (pintype "power_in"))
      (node (ref "U7B") (pin "3") (pinfunction "VDD_3") (pintype "power_in"))
      (node (ref "X6") (pin "1") (pinfunction "1_1") (pintype "passive"))
    )
    (net (code "3") (name "+12V") (class "Default")
      (node (ref "C10") (pin "1") (pinfunction "1_1") (pintype "passive"))
      (node (ref "C6") (pin "1") (pinfunction "1_1") (pintype "passive"))
      (node (ref "C7") (pin "1") (pinfunction "1_1") (pintype "passive"))
      (node (ref "J3") (pin "1") (pinfunction "1_1") (pintype "passive"))
      (node (ref "JP2") (pin "7") (pinfunction "7_7") (pintype "passive"))
      (node (ref "JP4") (pin "2") (pinfunction "2_2") (pintype "passive"))
      (node (ref "SJ11") (pin "P$2") (pinfunction "2_P$2") (pintype "passive"))
      (node (ref "SJ14") (pin "P$2") (pinfunction "2_P$2") (pintype "passive"))
      (node (ref "SJ2") (pin "P$2") (pinfunction "2_P$2") (pintype "passive"))
      (node (ref "SJ5") (pin "P$2") (pinfunction "2_P$2") (pintype "passive"))
      (node (ref "SJ8") (pin "P$2") (pinfunction "2_P$2") (pintype "passive"))
      (node (ref "U10") (pin "4") (pinfunction "V+_4") (pintype "power_in"))
      (node (ref "U3") (pin "6") (pinfunction "VDD_6") (pintype "power_in"))
      (node (ref "U4") (pin "6") (pinfunction "VDD_6") (pintype "power_in"))
      (node (ref "U5") (pin "6") (pinfunction "VDD_6") (pintype "power_in"))
      (node (ref "U6") (pin "6") (pinfunction "VDD_6") (pintype "power_in"))
      (node (ref "U8") (pin "1") (pinfunction "VIN_1") (pintype "bidirectional"))
      (node (ref "U8B") (pin "5") (pinfunction "IN_5") (pintype "input"))
      (node (ref "U9") (pin "4") (pinfunction "V+_4") (pintype "power_in"))
    )
    (net (code "4") (name "/AGND") (class "Default")
      (node (ref "U$1") (pin "AGND") (pinfunction "AGND_AGND") (pintype "power_in"))
    )
    (net (code "5") (name "/AVDD") (class "Default")
      (node (ref "U$1") (pin "AVDD") (pinfunction "AVDD_AVDD") (pintype "power_in"))
    )
    (net (code "6") (name "/CANH") (class "Default")
      (node (ref "J1") (pin "1") (pinfunction "1_1") (pintype "passive"))
      (node (ref "J2") (pin "1") (pinfunction "1_1") (pintype "passive"))
      (node (ref "U7") (pin "7") (pinfunction "CANH_7") (pintype "bidirectional"))
      (node (ref "U7B") (pin "7") (pinfunction "CANH_7") (pintype "bidirectional"))
    )
    (net (code "7") (name "/CANL") (class "Default")
      (node (ref "J1") (pin "2") (pinfunction "2_2") (pintype "passive"))
      (node (ref "J2") (pin "2") (pinfunction "2_2") (pintype "passive"))
      (node (ref "U7") (pin "6") (pinfunction "CANL_6") (pintype "bidirectional"))
      (node (ref "U7B") (pin "6") (pinfunction "CANL_6") (pintype "bidirectional"))
    )
    (net (code "8") (name "/GND4") (class "Default")
      (node (ref "U$1") (pin "GND4") (pinfunction "GND4_GND4") (pintype "power_in"))
    )
    (net (code "9") (name "/PWR_POS") (class "Default")
      (node (ref "J1") (pin "8") (pinfunction "8_8") (pintype "passive"))
      (node (ref "J2") (pin "8") (pinfunction "8_8") (pintype "passive"))
      (node (ref "R40") (pin "2") (pinfunction "2_2") (pintype "passive"))
    )
    (net (code "10") (name "/U5V") (class "Default")
      (node (ref "U$1") (pin "U5V") (pinfunction "U5V_U5V") (pintype "power_in"))
    )
    (net (code "11") (name "/VBAT") (class "Default")
      (node (ref "U$1") (pin "VBAT") (pinfunction "VBAT_VBAT") (pintype "power_in"))
    )
    (net (code "12") (name "/VDD") (class "Default")
      (node (ref "U$1") (pin "VDD") (pinfunction "VDD_VDD") (pintype "power_in"))
    )
    (net (code "13") (name "CANRX") (class "Default")
      (node (ref "U$1") (pin "PB8") (pinfunction "PB8_PB8") (pintype "bidirectional"))
      (node (ref "U7") (pin "4") (pinfunction "RXD_4") (pintype "output"))
      (node (ref "U7B") (pin "4") (pinfunction "RXD_4") (pintype "bidirectional"))
    )
    (net (code "14") (name "CANTX") (class "Default")
      (node (ref "U$1") (pin "PB9") (pinfunction "PB9_PB9") (pintype "bidirectional"))
      (node (ref "U7") (pin "1") (pinfunction "TXD_1") (pintype "input"))
      (node (ref "U7B") (pin "1") (pinfunction "TXD_1") (pintype "bidirectional"))
    )
    (net (code "15") (name "E_CS") (class "Default")
      (node (ref "JP2") (pin "4") (pinfunction "4_4") (pintype "passive"))
      (node (ref "R23") (pin "2") (pinfunction "2_2") (pintype "passive"))
      (node (ref "U$1") (pin "PC10") (pinfunction "PC10_PC10") (pintype "bidirectional"))
    )
    (net (code "16") (name "E_LAT") (class "Default")
      (node (ref "JP2") (pin "5") (pinfunction "5_5") (pintype "passive"))
      (node (ref "R22") (pin "2") (pinfunction "2_2") (pintype "passive"))
      (node (ref "U$1") (pin "PC11") (pinfunction "PC11_PC11") (pintype "bidirectional"))
    )
    (net (code "17") (name "GND") (class "Default")
      (node (ref "C1") (pin "2") (pinfunction "2_2") (pintype "passive"))
      (node (ref "C10") (pin "2") (pinfunction "2_2") (pintype "passive"))
      (node (ref "C11") (pin "2") (pinfunction "2_2") (pintype "passive"))
      (node (ref "C2") (pin "-") (pinfunction "-_-") (pintype "passive"))
      (node (ref "C3") (pin "2") (pinfunction "2_2") (pintype "passive"))
      (node (ref "C4") (pin "2") (pinfunction "2_2") (pintype "passive"))
      (node (ref "C5") (pin "2") (pinfunction "2_2") (pintype "passive"))
      (node (ref "C6") (pin "2") (pinfunction "2_2") (pintype "passive"))
      (node (ref "C7") (pin "2") (pinfunction "2_2") (pintype "passive"))
      (node (ref "C8") (pin "2") (pinfunction "2_2") (pintype "passive"))
      (node (ref "C9") (pin "2") (pinfunction "2_2") (pintype "passive"))
      (node (ref "D1") (pin "A") (pinfunction "A_A") (pintype "passive"))
      (node (ref "D3") (pin "A") (pinfunction "A_A") (pintype "passive"))
      (node (ref "J1") (pin "3") (pinfunction "3_3") (pintype "passive"))
      (node (ref "J1") (pin "6") (pinfunction "6_6") (pintype "passive"))
      (node (ref "J1") (pin "7") (pinfunction "7_7") (pintype "passive"))
      (node (ref "J2") (pin "3") (pinfunction "3_3") (pintype "passive"))
      (node (ref "J2") (pin "6") (pinfunction "6_6") (pintype "passive"))
      (node (ref "J2") (pin "7") (pinfunction "7_7") (pintype "passive"))
      (node (ref "J3") (pin "2") (pinfunction "2_2") (pintype "passive"))
      (node (ref "J3") (pin "3") (pinfunction "3_3") (pintype "passive"))
      (node (ref "JP1") (pin "4") (pinfunction "4_4") (pintype "passive"))
      (node (ref "JP2") (pin "8") (pinfunction "8_8") (pintype "passive"))
      (node (ref "JP5") (pin "5") (pinfunction "5_5") (pintype "passive"))
      (node (ref "JP5") (pin "6") (pinfunction "6_6") (pintype "passive"))
      (node (ref "JP6") (pin "5") (pinfunction "5_5") (pintype "passive"))
      (node (ref "JP6") (pin "6") (pinfunction "6_6") (pintype "passive"))
      (node (ref "JP7") (pin "5") (pinfunction "5_5") (pintype "passive"))
      (node (ref "JP7") (pin "6") (pinfunction "6_6") (pintype "passive"))
      (node (ref "JP8") (pin "5") (pinfunction "5_5") (pintype "passive"))
      (node (ref "JP8") (pin "6") (pinfunction "6_6") (pintype "passive"))
      (node (ref "PORTA") (pin "5") (pinfunction "5_5") (pintype "passive"))
      (node (ref "PORTB") (pin "5") (pinfunction "5_5") (pintype "passive"))
      (node (ref "PORTC") (pin "5") (pinfunction "5_5") (pintype "passive"))
      (node (ref "Q1") (pin "2") (pinfunction "S_2") (pintype "passive"))
      (node (ref "Q10") (pin "2") (pinfunction "S_2") (pintype "passive"))
      (node (ref "Q11") (pin "2") (pinfunction "S_2") (pintype "passive"))
      (node (ref "Q12") (pin "2") (pinfunction "S_2") (pintype "passive"))
      (node (ref "Q13") (pin "2") (pinfunction "S_2") (pintype "passive"))
      (node (ref "Q14") (pin "2") (pinfunction "S_2") (pintype "passive"))
      (node (ref "Q15") (pin "2") (pinfunction "S_2") (pintype "passive"))
      (node (ref "Q16") (pin "2") (pinfunction "S_2") (pintype "passive"))
      (node (ref "Q2") (pin "2") (pinfunction "S_2") (pintype "passive"))
      (node (ref "Q3") (pin "2") (pinfunction "S_2") (pintype "passive"))
      (node (ref "Q4") (pin "2") (pinfunction "S_2") (pintype "passive"))
      (node (ref "Q5") (pin "2") (pinfunction "S_2") (pintype "passive"))
      (node (ref "Q6") (pin "2") (pinfunction "S_2") (pintype "passive"))
      (node (ref "Q7") (pin "2") (pinfunction "S_2") (pintype "passive"))
      (node (ref "Q8") (pin "2") (pinfunction "S_2") (pintype "passive"))
      (node (ref "Q9") (pin "2") (pinfunction "S_2") (pintype "passive"))
      (node (ref "R2") (pin "1") (pinfunction "1_1") (pintype "passive"))
      (node (ref "R61") (pin "2") (pinfunction "2_2") (pintype "passive"))
      (node (ref "SJ12") (pin "P$2") (pinfunction "2_P$2") (pintype "passive"))
      (node (ref "SJ3") (pin "2") (pinfunction "2_2") (pintype "passive"))
      (node (ref "SJ6") (pin "P$2") (pinfunction "2_P$2") (pintype "passive"))
      (node (ref "SJ9") (pin "2") (pinfunction "2_2") (pintype "passive"))
      (node (ref "U$1") (pin "GND3") (pinfunction "GND3_GND3") (pintype "power_in"))
      (node (ref "U$1") (pin "GND5") (pinfunction "GND5_GND5") (pintype "power_in"))
      (node (ref "U$1") (pin "GND6") (pinfunction "GND6_GND6") (pintype "power_in"))
      (node (ref "U$1") (pin "GND7") (pinfunction "GND7_GND7") (pintype "power_in"))
      (node (ref "U$1") (pin "GND8") (pinfunction "GND8_GND8") (pintype "power_in"))
      (node (ref "U1") (pin "6") (pinfunction "INH_6") (pintype "input"))
      (node (ref "U1") (pin "8") (pinfunction "GND_8") (pintype "power_in"))
      (node (ref "U10") (pin "11") (pinfunction "V-_11") (pintype "power_in"))
      (node (ref "U11") (pin "13") (pinfunction "G_13") (pintype "input"))
      (node (ref "U11") (pin "8") (pinfunction "GND_8") (pintype "power_in"))
      (node (ref "U13") (pin "13") (pinfunction "G_13") (pintype "input"))
      (node (ref "U13") (pin "8") (pinfunction "GND_8") (pintype "power_in"))
      (node (ref "U2") (pin "6") (pinfunction "INH_6") (pintype "input"))
      (node (ref "U2") (pin "8") (pinfunction "GND_8") (pintype "power_in"))
      (node (ref "U3") (pin "3") (pinfunction "VSS_3") (pintype "power_in"))
      (node (ref "U4") (pin "3") (pinfunction "VSS_3") (pintype "power_in"))
      (node (ref "U5") (pin "3") (pinfunction "VSS_3") (pintype "power_in"))
      (node (ref "U6") (pin "3") (pinfunction "VSS_3") (pintype "power_in"))
      (node (ref "U7") (pin "2") (pinfunction "GND_2") (pintype "power_in"))
      (node (ref "U7B") (pin "2") (pinfunction "VSS_2") (pintype "power_in"))
      (node (ref "U8") (pin "4") (pinfunction "SD_4") (pintype "bidirectional"))
      (node (ref "U8") (pin "5") (pinfunction "GND1_5") (pintype "power_in"))
      (node (ref "U8") (pin "6") (pinfunction "GND2_6") (pintype "power_in"))
      (node (ref "U8") (pin "7") (pinfunction "GND3_7") (pintype "power_in"))
      (node (ref "U8") (pin "8") (pinfunction "GND4_8") (pintype "power_in"))
      (node (ref "U8B") (pin "2") (pinfunction "GNDSIG_2") (pintype "input"))
      (node (ref "U8B") (pin "3") (pinfunction "~{ON/OFF}_3") (pintype "input"))
      (node (ref "U8B") (pin "4") (pinfunction "GND_4") (pintype "power_in"))
      (node (ref "U9") (pin "11") (pinfunction "V-_11") (pintype "power_in"))
      (node (ref "X6") (pin "2") (pinfunction "2_2") (pintype "passive"))
    )
    (net (code "18") (name "I2CSCL") (class "Default")
      (node (ref "JP1") (pin "1") (pinfunction "1_1") (pintype "passive"))
      (node (ref "R62") (pin "2") (pinfunction "2_2") (pintype "passive"))
      (node (ref "U$1") (pin "PB6") (pinfunction "PB6_PB6") (pintype "bidirectional"))
    )
    (net (code "19") (name "I2CSDA") (class "Default")
      (node (ref "JP1") (pin "2") (pinfunction "2_2") (pintype "passive"))
      (node (ref "R63") (pin "2") (pinfunction "2_2") (pintype "passive"))
      (node (ref "U$1") (pin "PB7") (pinfunction "PB7_PB7") (pintype "bidirectional"))
    )
    (net (code "20") (name "ILAT") (class "Default")
      (node (ref "U$1") (pin "PA6") (pinfunction "PA6_PA6") (pintype "bidirectional"))
      (node (ref "U1") (pin "15") (pinfunction "SH/~{LD}_15") (pintype "input"))
      (node (ref "U2") (pin "15") (pinfunction "SH/~{LD}_15") (pintype "input"))
    )
    (net (code "21") (name "MISO") (class "Default")
      (node (ref "JP2") (pin "1") (pinfunction "1_1") (pintype "passive"))
      (node (ref "U$1") (pin "PB4") (pinfunction "PB4_PB4") (pintype "bidirectional"))
    )
    (net (code "22") (name "MISO2") (class "Default")
      (node (ref "SJ13") (pin "P$2") (pinfunction "2_P$2") (pintype "passive"))
      (node (ref "SJ19") (pin "P$2") (pinfunction "2_P$2") (pintype "passive"))
      (node (ref "U$1") (pin "PC2") (pinfunction "PC2_PC2") (pintype "bidirectional"))
      (node (ref "U2") (pin "13") (pinfunction "QH_13") (pintype "output"))
    )
    (net (code "23") (name "MOSI") (class "Default")
      (node (ref "R20") (pin "1") (pinfunction "1_1") (pintype "passive"))
      (node (ref "SJ15") (pin "1") (pinfunction "1_1") (pintype "passive"))
      (node (ref "SJ17") (pin "P$2") (pinfunction "2_P$2") (pintype "passive"))
      (node (ref "U$1") (pin "PB5") (pinfunction "PB5_PB5") (pintype "bidirectional"))
      (node (ref "U11") (pin "14") (pinfunction "SER_14") (pintype "input"))
    )
    (net (code "24") (name "Net-(D2-PadA)") (class "Default")
      (node (ref "D2") (pin "A") (pinfunction "A_A") (pintype "passive"))
      (node (ref "D4") (pin "A") (pinfunction "A_A") (pintype "passive"))
      (node (ref "JP4") (pin "4") (pinfunction "4_4") (pintype "passive"))
    )
    (net (code "25") (name "Net-(D2-PadC)") (class "Default")
      (node (ref "D2") (pin "C") (pinfunction "C_C") (pintype "passive"))
      (node (ref "D4") (pin "C") (pinfunction "C_C") (pintype "passive"))
      (node (ref "JP4") (pin "1") (pinfunction "1_1") (pintype "passive"))
    )
    (net (code "26") (name "Net-(J1-Pad4)") (class "Default")
      (node (ref "J1") (pin "4") (pinfunction "4_4") (pintype "passive"))
      (node (ref "J2") (pin "4") (pinfunction "4_4") (pintype "passive"))
    )
    (net (code "27") (name "Net-(J1-Pad5)") (class "Default")
      (node (ref "J1") (pin "5") (pinfunction "5_5") (pintype "passive"))
      (node (ref "J2") (pin "5") (pinfunction "5_5") (pintype "passive"))
    )
    (net (code "28") (name "Net-(JP4-Pad3)") (class "Default")
      (node (ref "JP4") (pin "3") (pinfunction "3_3") (pintype "passive"))
      (node (ref "R40") (pin "1") (pinfunction "1_1") (pintype "passive"))
    )
    (net (code "29") (name "Net-(PORTA-Pad1)") (class "Default")
      (node (ref "PORTA") (pin "1") (pinfunction "1_1") (pintype "passive"))
      (node (ref "R44") (pin "2") (pinfunction "2_2") (pintype "passive"))
      (node (ref "R53") (pin "2") (pinfunction "2_2") (pintype "passive"))
      (node (ref "RN3") (pin "1") (pinfunction "1_1") (pintype "passive"))
      (node (ref "RN4") (pin "9") (pinfunction "9_9") (pintype "passive"))
      (node (ref "X1") (pin "1") (pinfunction "1_1") (pintype "passive"))
    )
    (net (code "30") (name "Net-(PORTB-Pad1)") (class "Default")
      (node (ref "PORTB") (pin "1") (pinfunction "1_1") (pintype "passive"))
      (node (ref "R35") (pin "2") (pinfunction "2_2") (pintype "passive"))
      (node (ref "R45") (pin "2") (pinfunction "2_2") (pintype "passive"))
      (node (ref "RN1") (pin "1") (pinfunction "1_1") (pintype "passive"))
      (node (ref "RN2") (pin "9") (pinfunction "9_9") (pintype "passive"))
      (node (ref "X2") (pin "1") (pinfunction "1_1") (pintype "passive"))
    )
    (net (code "31") (name "Net-(Q1-D)") (class "Default")
      (node (ref "Q1") (pin "3") (pinfunction "D_3") (pintype "passive"))
      (node (ref "U12") (pin "18") (pinfunction "O1_18") (pintype "open_collector"))
      (node (ref "X5") (pin "1") (pinfunction "1_1") (pintype "passive"))
    )
    (net (code "32") (name "Net-(Q1-G)") (class "Default")
      (node (ref "Q1") (pin "1") (pinfunction "G_1") (pintype "passive"))
      (node (ref "R3") (pin "2") (pinfunction "2_2") (pintype "passive"))
    )
    (net (code "33") (name "Net-(Q2-D)") (class "Default")
      (node (ref "Q2") (pin "3") (pinfunction "D_3") (pintype "passive"))
      (node (ref "U12") (pin "17") (pinfunction "O2_17") (pintype "open_collector"))
      (node (ref "X5") (pin "2") (pinfunction "2_2") (pintype "passive"))
    )
    (net (code "34") (name "Net-(Q2-G)") (class "Default")
      (node (ref "Q2") (pin "1") (pinfunction "G_1") (pintype "passive"))
      (node (ref "R4") (pin "2") (pinfunction "2_2") (pintype "passive"))
    )
    (net (code "35") (name "Net-(Q3-D)") (class "Default")
      (node (ref "Q3") (pin "3") (pinfunction "D_3") (pintype "passive"))
      (node (ref "U12") (pin "16") (pinfunction "O3_16") (pintype "open_collector"))
      (node (ref "X5") (pin "3") (pinfunction "3_3") (pintype "passive"))
    )
    (net (code "36") (name "Net-(Q3-G)") (class "Default")
      (node (ref "Q3") (pin "1") (pinfunction "G_1") (pintype "passive"))
      (node (ref "R5") (pin "2") (pinfunction "2_2") (pintype "passive"))
    )
    (net (code "37") (name "Net-(Q4-D)") (class "Default")
      (node (ref "Q4") (pin "3") (pinfunction "D_3") (pintype "passive"))
      (node (ref "U12") (pin "15") (pinfunction "O4_15") (pintype "open_collector"))
      (node (ref "X5") (pin "4") (pinfunction "4_4") (pintype "passive"))
    )
    (net (code "38") (name "Net-(Q4-G)") (class "Default")
      (node (ref "Q4") (pin "1") (pinfunction "G_1") (pintype "passive"))
      (node (ref "R6") (pin "2") (pinfunction "2_2") (pintype "passive"))
    )
    (net (code "39") (name "Net-(Q5-D)") (class "Default")
      (node (ref "Q5") (pin "3") (pinfunction "D_3") (pintype "passive"))
      (node (ref "U12") (pin "14") (pinfunction "O5_14") (pintype "open_collector"))
      (node (ref "X5") (pin "5") (pinfunction "5_5") (pintype "passive"))
    )
    (net (code "40") (name "Net-(Q5-G)") (class "Default")
      (node (ref "Q5") (pin "1") (pinfunction "G_1") (pintype "passive"))
      (node (ref "R7") (pin "2") (pinfunction "2_2") (pintype "passive"))
    )
    (net (code "41") (name "Net-(Q6-D)") (class "Default")
      (node (ref "Q6") (pin "3") (pinfunction "D_3") (pintype "passive"))
      (node (ref "U12") (pin "13") (pinfunction "O6_13") (pintype "open_collector"))
      (node (ref "X5") (pin "6") (pinfunction "6_6") (pintype "passive"))
    )
    (net (code "42") (name "Net-(Q6-G)") (class "Default")
      (node (ref "Q6") (pin "1") (pinfunction "G_1") (pintype "passive"))
      (node (ref "R8") (pin "2") (pinfunction "2_2") (pintype "passive"))
    )
    (net (code "43") (name "Net-(Q7-D)") (class "Default")
      (node (ref "Q7") (pin "3") (pinfunction "D_3") (pintype "passive"))
      (node (ref "U12") (pin "12") (pinfunction "O7_12") (pintype "open_collector"))
      (node (ref "X5") (pin "7") (pinfunction "7_7") (pintype "passive"))
    )
    (net (code "44") (name "Net-(Q7-G)") (class "Default")
      (node (ref "Q7") (pin "1") (pinfunction "G_1") (pintype "passive"))
      (node (ref "R9") (pin "2") (pinfunction "2_2") (pintype "passive"))
    )
    (net (code "45") (name "Net-(Q8-D)") (class "Default")
      (node (ref "Q8") (pin "3") (pinfunction "D_3") (pintype "passive"))
      (node (ref "U12") (pin "11") (pinfunction "O8_11") (pintype "open_collector"))
      (node (ref "X5") (pin "8") (pinfunction "8_8") (pintype "passive"))
    )
    (net (code "46") (name "Net-(Q8-G)") (class "Default")
      (node (ref "Q8") (pin "1") (pinfunction "G_1") (pintype "passive"))
      (node (ref "R10") (pin "2") (pinfunction "2_2") (pintype "passive"))
    )
    (net (code "47") (name "Net-(Q9-D)") (class "Default")
      (node (ref "Q9") (pin "3") (pinfunction "D_3") (pintype "passive"))
      (node (ref "U14") (pin "18") (pinfunction "O1_18") (pintype "open_collector"))
      (node (ref "X4") (pin "1") (pinfunction "1_1") (pintype "passive"))
    )
    (net (code "48") (name "Net-(Q9-G)") (class "Default")
      (node (ref "Q9") (pin "1") (pinfunction "G_1") (pintype "passive"))
      (node (ref "R11") (pin "2") (pinfunction "2_2") (pintype "passive"))
    )
    (net (code "49") (name "Net-(Q10-D)") (class "Default")
      (node (ref "Q10") (pin "3") (pinfunction "D_3") (pintype "passive"))
      (node (ref "U14") (pin "17") (pinfunction "O2_17") (pintype "open_collector"))
      (node (ref "X4") (pin "2") (pinfunction "2_2") (pintype "passive"))
    )
    (net (code "50") (name "Net-(Q10-G)") (class "Default")
      (node (ref "Q10") (pin "1") (pinfunction "G_1") (pintype "passive"))
      (node (ref "R12") (pin "2") (pinfunction "2_2") (pintype "passive"))
    )
    (net (code "51") (name "Net-(Q11-D)") (class "Default")
      (node (ref "Q11") (pin "3") (pinfunction "D_3") (pintype "passive"))
      (node (ref "U14") (pin "16") (pinfunction "O3_16") (pintype "open_collector"))
      (node (ref "X4") (pin "3") (pinfunction "3_3") (pintype "passive"))
    )
    (net (code "52") (name "Net-(Q11-G)") (class "Default")
      (node (ref "Q11") (pin "1") (pinfunction "G_1") (pintype "passive"))
      (node (ref "R13") (pin "2") (pinfunction "2_2") (pintype "passive"))
    )
    (net (code "53") (name "Net-(Q12-D)") (class "Default")
      (node (ref "Q12") (pin "3") (pinfunction "D_3") (pintype "passive"))
      (node (ref "U14") (pin "15") (pinfunction "O4_15") (pintype "open_collector"))
      (node (ref "X4") (pin "4") (pinfunction "4_4") (pintype "passive"))
    )
    (net (code "54") (name "Net-(Q12-G)") (class "Default")
      (node (ref "Q12") (pin "1") (pinfunction "G_1") (pintype "passive"))
      (node (ref "R14") (pin "2") (pinfunction "2_2") (pintype "passive"))
    )
    (net (code "55") (name "Net-(Q13-D)") (class "Default")
      (node (ref "Q13") (pin "3") (pinfunction "D_3") (pintype "passive"))
      (node (ref "U14") (pin "14") (pinfunction "O5_14") (pintype "open_collector"))
      (node (ref "X4") (pin "5") (pinfunction "5_5") (pintype "passive"))
    )
    (net (code "56") (name "Net-(Q13-G)") (class "Default")
      (node (ref "Q13") (pin "1") (pinfunction "G_1") (pintype "passive"))
      (node (ref "R15") (pin "2") (pinfunction "2_2") (pintype "passive"))
    )
    (net (code "57") (name "Net-(Q14-D)") (class "Default")
      (node (ref "Q14") (pin "3") (pinfunction "D_3") (pintype "passive"))
      (node (ref "U14") (pin "13") (pinfunction "O6_13") (pintype "open_collector"))
      (node (ref "X4") (pin "6") (pinfunction "6_6") (pintype "passive"))
    )
    (net (code "58") (name "Net-(Q14-G)") (class "Default")
      (node (ref "Q14") (pin "1") (pinfunction "G_1") (pintype "passive"))
      (node (ref "R16") (pin "2") (pinfunction "2_2") (pintype "passive"))
    )
    (net (code "59") (name "Net-(Q15-D)") (class "Default")
      (node (ref "Q15") (pin "3") (pinfunction "D_3") (pintype "passive"))
      (node (ref "U14") (pin "12") (pinfunction "O7_12") (pintype "open_collector"))
      (node (ref "X4") (pin "7") (pinfunction "7_7") (pintype "passive"))
    )
    (net (code "60") (name "Net-(Q15-G)") (class "Default")
      (node (ref "Q15") (pin "1") (pinfunction "G_1") (pintype "passive"))
      (node (ref "R17") (pin "2") (pinfunction "2_2") (pintype "passive"))
    )
    (net (code "61") (name "Net-(Q16-D)") (class "Default")
      (node (ref "Q16") (pin "3") (pinfunction "D_3") (pintype "passive"))
      (node (ref "U14") (pin "11") (pinfunction "O8_11") (pintype "open_collector"))
      (node (ref "X4") (pin "8") (pinfunction "8_8") (pintype "passive"))
    )
    (net (code "62") (name "Net-(Q16-G)") (class "Default")
      (node (ref "Q16") (pin "1") (pinfunction "G_1") (pintype "passive"))
      (node (ref "R18") (pin "2") (pinfunction "2_2") (pintype "passive"))
    )
    (net (code "63") (name "Net-(RN1A-2)") (class "Default")
      (node (ref "R35") (pin "1") (pinfunction "1_1") (pintype "passive"))
      (node (ref "RN1") (pin "16") (pinfunction "2_16") (pintype "passive"))
      (node (ref "U2") (pin "14") (pinfunction "H_14") (pintype "input"))
    )
    (net (code "64") (name "Net-(RN1B-1)") (class "Default")
      (node (ref "PORTB") (pin "2") (pinfunction "2_2") (pintype "passive"))
      (node (ref "R34") (pin "2") (pinfunction "2_2") (pintype "passive"))
      (node (ref "R46") (pin "2") (pinfunction "2_2") (pintype "passive"))
      (node (ref "RN1") (pin "2") (pinfunction "1_2") (pintype "passive"))
      (node (ref "RN2") (pin "8") (pinfunction "8_8") (pintype "passive"))
      (node (ref "X2") (pin "2") (pinfunction "2_2") (pintype "passive"))
    )
    (net (code "65") (name "Net-(RN1B-2)") (class "Default")
      (node (ref "R34") (pin "1") (pinfunction "1_1") (pintype "passive"))
      (node (ref "RN1") (pin "15") (pinfunction "2_15") (pintype "passive"))
      (node (ref "U2") (pin "12") (pinfunction "G_12") (pintype "input"))
    )
    (net (code "66") (name "Net-(RN1C-1)") (class "Default")
      (node (ref "PORTB") (pin "3") (pinfunction "3_3") (pintype "passive"))
      (node (ref "R33") (pin "2") (pinfunction "2_2") (pintype "passive"))
      (node (ref "R47") (pin "2") (pinfunction "2_2") (pintype "passive"))
      (node (ref "RN1") (pin "3") (pinfunction "1_3") (pintype "passive"))
      (node (ref "RN2") (pin "7") (pinfunction "7_7") (pintype "passive"))
      (node (ref "X2") (pin "3") (pinfunction "3_3") (pintype "passive"))
    )
    (net (code "67") (name "Net-(RN1C-2)") (class "Default")
      (node (ref "R33") (pin "1") (pinfunction "1_1") (pintype "passive"))
      (node (ref "RN1") (pin "14") (pinfunction "2_14") (pintype "passive"))
      (node (ref "U2") (pin "11") (pinfunction "F_11") (pintype "input"))
    )
    (net (code "68") (name "Net-(RN1D-1)") (class "Default")
      (node (ref "PORTB") (pin "4") (pinfunction "4_4") (pintype "passive"))
      (node (ref "R32") (pin "2") (pinfunction "2_2") (pintype "passive"))
      (node (ref "R48") (pin "2") (pinfunction "2_2") (pintype "passive"))
      (node (ref "RN1") (pin "4") (pinfunction "1_4") (pintype "passive"))
      (node (ref "RN2") (pin "6") (pinfunction "6_6") (pintype "passive"))
      (node (ref "X2") (pin "4") (pinfunction "4_4") (pintype "passive"))
    )
    (net (code "69") (name "Net-(RN1D-2)") (class "Default")
      (node (ref "R32") (pin "1") (pinfunction "1_1") (pintype "passive"))
      (node (ref "RN1") (pin "13") (pinfunction "2_13") (pintype "passive"))
      (node (ref "U2") (pin "10") (pinfunction "E_10") (pintype "input"))
    )
    (net (code "70") (name "Net-(RN1E-1)") (class "Default")
      (node (ref "PORTB") (pin "7") (pinfunction "7_7") (pintype "passive"))
      (node (ref "R31") (pin "2") (pinfunction "2_2") (pintype "passive"))
      (node (ref "R49") (pin "2") (pinfunction "2_2") (pintype "passive"))
      (node (ref "RN1") (pin "5") (pinfunction "1_5") (pintype "passive"))
      (node (ref "RN2") (pin "5") (pinfunction "5_5") (pintype "passive"))
      (node (ref "X2") (pin "5") (pinfunction "5_5") (pintype "passive"))
    )
    (net (code "71") (name "Net-(RN1E-2)") (class "Default")
      (node (ref "R31") (pin "1") (pinfunction "1_1") (pintype "passive"))
      (node (ref "RN1") (pin "12") (pinfunction "2_12") (pintype "passive"))
      (node (ref "U2") (pin "5") (pinfunction "D_5") (pintype "input"))
    )
    (net (code "72") (name "Net-(RN1F-1)") (class "Default")
      (node (ref "PORTB") (pin "8") (pinfunction "8_8") (pintype "passive"))
      (node (ref "R30") (pin "2") (pinfunction "2_2") (pintype "passive"))
      (node (ref "R50") (pin "2") (pinfunction "2_2") (pintype "passive"))
      (node (ref "RN1") (pin "6") (pinfunction "1_6") (pintype "passive"))
      (node (ref "RN2") (pin "4") (pinfunction "4_4") (pintype "passive"))
      (node (ref "X2") (pin "6") (pinfunction "6_6") (pintype "passive"))
    )
    (net (code "73") (name "Net-(RN1F-2)") (class "Default")
      (node (ref "R30") (pin "1") (pinfunction "1_1") (pintype "passive"))
      (node (ref "RN1") (pin "11") (pinfunction "2_11") (pintype "passive"))
      (node (ref "U2") (pin "4") (pinfunction "C_4") (pintype "input"))
    )
    (net (code "74") (name "Net-(RN1G-1)") (class "Default")
      (node (ref "PORTB") (pin "9") (pinfunction "9_9") (pintype "passive"))
      (node (ref "R29") (pin "2") (pinfunction "2_2") (pintype "passive"))
      (node (ref "R51") (pin "2") (pinfunction "2_2") (pintype "passive"))
      (node (ref "RN1") (pin "7") (pinfunction "1_7") (pintype "passive"))
      (node (ref "RN2") (pin "3") (pinfunction "3_3") (pintype "passive"))
      (node (ref "X2") (pin "7") (pinfunction "7_7") (pintype "passive"))
    )
    (net (code "75") (name "Net-(RN1G-2)") (class "Default")
      (node (ref "R29") (pin "1") (pinfunction "1_1") (pintype "passive"))
      (node (ref "RN1") (pin "10") (pinfunction "2_10") (pintype "passive"))
      (node (ref "U2") (pin "3") (pinfunction "B_3") (pintype "input"))
    )
    (net (code "76") (name "Net-(RN1H-1)") (class "Default")
      (node (ref "PORTB") (pin "10") (pinfunction "10_10") (pintype "passive"))
      (node (ref "R28") (pin "2") (pinfunction "2_2") (pintype "passive"))
      (node (ref "R52") (pin "2") (pinfunction "2_2") (pintype "passive"))
      (node (ref "RN1") (pin "8") (pinfunction "1_8") (pintype "passive"))
      (node (ref "RN2") (pin "2") (pinfunction "2_2") (pintype "passive"))
      (node (ref "X2") (pin "8") (pinfunction "8_8") (pintype "passive"))
    )
    (net (code "77") (name "Net-(RN1H-2)") (class "Default")
      (node (ref "R28") (pin "1") (pinfunction "1_1") (pintype "passive"))
      (node (ref "RN1") (pin "9") (pinfunction "2_9") (pintype "passive"))
      (node (ref "U2") (pin "2") (pinfunction "A_2") (pintype "input"))
    )
    (net (code "78") (name "Net-(RN3A-2)") (class "Default")
      (node (ref "R44") (pin "1") (pinfunction "1_1") (pintype "passive"))
      (node (ref "RN3") (pin "16") (pinfunction "2_16") (pintype "passive"))
      (node (ref "U1") (pin "14") (pinfunction "H_14") (pintype "input"))
    )
    (net (code "79") (name "Net-(RN3B-1)") (class "Default")
      (node (ref "PORTA") (pin "2") (pinfunction "2_2") (pintype "passive"))
      (node (ref "R43") (pin "2") (pinfunction "2_2") (pintype "passive"))
      (node (ref "R54") (pin "2") (pinfunction "2_2") (pintype "passive"))
      (node (ref "RN3") (pin "2") (pinfunction "1_2") (pintype "passive"))
      (node (ref "RN4") (pin "8") (pinfunction "8_8") (pintype "passive"))
      (node (ref "X1") (pin "2") (pinfunction "2_2") (pintype "passive"))
    )
    (net (code "80") (name "Net-(RN3B-2)") (class "Default")
      (node (ref "R43") (pin "1") (pinfunction "1_1") (pintype "passive"))
      (node (ref "RN3") (pin "15") (pinfunction "2_15") (pintype "passive"))
      (node (ref "U1") (pin "12") (pinfunction "G_12") (pintype "input"))
    )
    (net (code "81") (name "Net-(RN3C-1)") (class "Default")
      (node (ref "PORTA") (pin "3") (pinfunction "3_3") (pintype "passive"))
      (node (ref "R42") (pin "2") (pinfunction "2_2") (pintype "passive"))
      (node (ref "R55") (pin "2") (pinfunction "2_2") (pintype "passive"))
      (node (ref "RN3") (pin "3") (pinfunction "1_3") (pintype "passive"))
      (node (ref "RN4") (pin "7") (pinfunction "7_7") (pintype "passive"))
      (node (ref "X1") (pin "3") (pinfunction "3_3") (pintype "passive"))
    )
    (net (code "82") (name "Net-(RN3C-2)") (class "Default")
      (node (ref "R42") (pin "1") (pinfunction "1_1") (pintype "passive"))
      (node (ref "RN3") (pin "14") (pinfunction "2_14") (pintype "passive"))
      (node (ref "U1") (pin "11") (pinfunction "F_11") (pintype "input"))
    )
    (net (code "83") (name "Net-(RN3D-1)") (class "Default")
      (node (ref "PORTA") (pin "4") (pinfunction "4_4") (pintype "passive"))
      (node (ref "R41") (pin "2") (pinfunction "2_2") (pintype "passive"))
      (node (ref "R56") (pin "2") (pinfunction "2_2") (pintype "passive"))
      (node (ref "RN3") (pin "4") (pinfunction "1_4") (pintype "passive"))
      (node (ref "RN4") (pin "6") (pinfunction "6_6") (pintype "passive"))
      (node (ref "X1") (pin "4") (pinfunction "4_4") (pintype "passive"))
    )
    (net (code "84") (name "Net-(RN3D-2)") (class "Default")
      (node (ref "R41") (pin "1") (pinfunction "1_1") (pintype "passive"))
      (node (ref "RN3") (pin "13") (pinfunction "2_13") (pintype "passive"))
      (node (ref "U1") (pin "10") (pinfunction "E_10") (pintype "input"))
    )
    (net (code "85") (name "Net-(RN3E-1)") (class "Default")
      (node (ref "PORTA") (pin "7") (pinfunction "7_7") (pintype "passive"))
      (node (ref "R39") (pin "2") (pinfunction "2_2") (pintype "passive"))
      (node (ref "R57") (pin "2") (pinfunction "2_2") (pintype "passive"))
      (node (ref "RN3") (pin "5") (pinfunction "1_5") (pintype "passive"))
      (node (ref "RN4") (pin "5") (pinfunction "5_5") (pintype "passive"))
      (node (ref "X1") (pin "5") (pinfunction "5_5") (pintype "passive"))
    )
    (net (code "86") (name "Net-(RN3E-2)") (class "Default")
      (node (ref "R39") (pin "1") (pinfunction "1_1") (pintype "passive"))
      (node (ref "RN3") (pin "12") (pinfunction "2_12") (pintype "passive"))
      (node (ref "U1") (pin "5") (pinfunction "D_5") (pintype "input"))
    )
    (net (code "87") (name "Net-(RN3F-1)") (class "Default")
      (node (ref "PORTA") (pin "8") (pinfunction "8_8") (pintype "passive"))
      (node (ref "R38") (pin "2") (pinfunction "2_2") (pintype "passive"))
      (node (ref "R58") (pin "2") (pinfunction "2_2") (pintype "passive"))
      (node (ref "RN3") (pin "6") (pinfunction "1_6") (pintype "passive"))
      (node (ref "RN4") (pin "4") (pinfunction "4_4") (pintype "passive"))
      (node (ref "X1") (pin "6") (pinfunction "6_6") (pintype "passive"))
    )
    (net (code "88") (name "Net-(RN3F-2)") (class "Default")
      (node (ref "R38") (pin "1") (pinfunction "1_1") (pintype "passive"))
      (node (ref "RN3") (pin "11") (pinfunction "2_11") (pintype "passive"))
      (node (ref "U1") (pin "4") (pinfunction "C_4") (pintype "input"))
    )
    (net (code "89") (name "Net-(RN3G-1)") (class "Default")
      (node (ref "PORTA") (pin "9") (pinfunction "9_9") (pintype "passive"))
      (node (ref "R37") (pin "2") (pinfunction "2_2") (pintype "passive"))
      (node (ref "R59") (pin "2") (pinfunction "2_2") (pintype "passive"))
      (node (ref "RN3") (pin "7") (pinfunction "1_7") (pintype "passive"))
      (node (ref "RN4") (pin "3") (pinfunction "3_3") (pintype "passive"))
      (node (ref "X1") (pin "7") (pinfunction "7_7") (pintype "passive"))
    )
    (net (code "90") (name "Net-(RN3G-2)") (class "Default")
      (node (ref "R37") (pin "1") (pinfunction "1_1") (pintype "passive"))
      (node (ref "RN3") (pin "10") (pinfunction "2_10") (pintype "passive"))
      (node (ref "U1") (pin "3") (pinfunction "B_3") (pintype "input"))
    )
    (net (code "91") (name "Net-(RN3H-1)") (class "Default")
      (node (ref "PORTA") (pin "10") (pinfunction "10_10") (pintype "passive"))
      (node (ref "R36") (pin "2") (pinfunction "2_2") (pintype "passive"))
      (node (ref "R60") (pin "2") (pinfunction "2_2") (pintype "passive"))
      (node (ref "RN3") (pin "8") (pinfunction "1_8") (pintype "passive"))
      (node (ref "RN4") (pin "2") (pinfunction "2_2") (pintype "passive"))
      (node (ref "X1") (pin "8") (pinfunction "8_8") (pintype "passive"))
    )
    (net (code "92") (name "Net-(RN3H-2)") (class "Default")
      (node (ref "R36") (pin "1") (pinfunction "1_1") (pintype "passive"))
      (node (ref "RN3") (pin "9") (pinfunction "2_9") (pintype "passive"))
      (node (ref "U1") (pin "2") (pinfunction "A_2") (pintype "input"))
    )
    (net (code "93") (name "Net-(SJ1-1)") (class "Default")
      (node (ref "SJ1") (pin "P$1") (pinfunction "1_P$1") (pintype "passive"))
      (node (ref "SJ2") (pin "P$1") (pinfunction "1_P$1") (pintype "passive"))
      (node (ref "SJ3") (pin "1") (pinfunction "1_1") (pintype "passive"))
      (node (ref "U12") (pin "9") (pinfunction "GND_9") (pintype "power_in"))
    )
    (net (code "94") (name "Net-(SJ4-1)") (class "Default")
      (node (ref "SJ4") (pin "P$1") (pinfunction "1_P$1") (pintype "passive"))
      (node (ref "SJ5") (pin "P$1") (pinfunction "1_P$1") (pintype "passive"))
      (node (ref "SJ6") (pin "P$1") (pinfunction "1_P$1") (pintype "passive"))
      (node (ref "U12") (pin "10") (pinfunction "CD+_10") (pintype "passive"))
    )
    (net (code "95") (name "Net-(SJ7-1)") (class "Default")
      (node (ref "SJ7") (pin "P$1") (pinfunction "1_P$1") (pintype "passive"))
      (node (ref "SJ8") (pin "P$1") (pinfunction "1_P$1") (pintype "passive"))
      (node (ref "SJ9") (pin "1") (pinfunction "1_1") (pintype "passive"))
      (node (ref "U14") (pin "9") (pinfunction "GND_9") (pintype "power_in"))
    )
    (net (code "96") (name "Net-(SJ10-1)") (class "Default")
      (node (ref "SJ10") (pin "P$1") (pinfunction "1_P$1") (pintype "passive"))
      (node (ref "SJ11") (pin "P$1") (pinfunction "1_P$1") (pintype "passive"))
      (node (ref "SJ12") (pin "P$1") (pinfunction "1_P$1") (pintype "passive"))
      (node (ref "U14") (pin "10") (pinfunction "CD+_10") (pintype "passive"))
    )
    (net (code "97") (name "Net-(SJ13-1)") (class "Default")
      (node (ref "SJ13") (pin "P$1") (pinfunction "1_P$1") (pintype "passive"))
      (node (ref "U$1") (pin "PB14") (pinfunction "PB14_PB14") (pintype "bidirectional"))
    )
    (net (code "98") (name "Net-(SJ14-1)") (class "Default")
      (node (ref "SJ14") (pin "P$1") (pinfunction "1_P$1") (pintype "passive"))
      (node (ref "U$1") (pin "VIN2") (pinfunction "VIN2_VIN2") (pintype "power_in"))
    )
    (net (code "99") (name "Net-(SJ16-2)") (class "Default")
      (node (ref "JP2") (pin "2") (pinfunction "2_2") (pintype "passive"))
      (node (ref "SJ15") (pin "2") (pinfunction "2_2") (pintype "passive"))
      (node (ref "SJ16") (pin "P$2") (pinfunction "2_P$2") (pintype "passive"))
    )
    (net (code "100") (name "Net-(SJ18-2)") (class "Default")
      (node (ref "SJ18") (pin "P$2") (pinfunction "2_P$2") (pintype "passive"))
      (node (ref "U7") (pin "5") (pinfunction "VREF_5") (pintype "output"))
      (node (ref "U7B") (pin "5") (pinfunction "VREF_5") (pintype "bidirectional"))
    )
    (net (code "101") (name "Net-(U3A-O)") (class "Default")
      (node (ref "PORTC") (pin "1") (pinfunction "1_1") (pintype "passive"))
      (node (ref "U3") (pin "7") (pinfunction "O_7") (pintype "output"))
      (node (ref "U9") (pin "7") (pinfunction "OUT_7") (pintype "output"))
      (node (ref "X3") (pin "1") (pinfunction "1_1") (pintype "passive"))
    )
    (net (code "102") (name "Net-(U3B-O)") (class "Default")
      (node (ref "PORTC") (pin "2") (pinfunction "2_2") (pintype "passive"))
      (node (ref "U3") (pin "5") (pinfunction "O_5") (pintype "output"))
      (node (ref "U9") (pin "8") (pinfunction "OUT_8") (pintype "output"))
      (node (ref "X3") (pin "2") (pinfunction "2_2") (pintype "passive"))
    )
    (net (code "103") (name "Net-(U4A-O)") (class "Default")
      (node (ref "PORTC") (pin "4") (pinfunction "4_4") (pintype "passive"))
      (node (ref "U4") (pin "7") (pinfunction "O_7") (pintype "output"))
      (node (ref "U9") (pin "14") (pinfunction "OUT_14") (pintype "output"))
      (node (ref "X3") (pin "4") (pinfunction "4_4") (pintype "passive"))
    )
    (net (code "104") (name "Net-(U4B-O)") (class "Default")
      (node (ref "PORTC") (pin "3") (pinfunction "3_3") (pintype "passive"))
      (node (ref "U4") (pin "5") (pinfunction "O_5") (pintype "output"))
      (node (ref "U9") (pin "1") (pinfunction "OUT_1") (pintype "output"))
      (node (ref "X3") (pin "3") (pinfunction "3_3") (pintype "passive"))
    )
    (net (code "105") (name "Net-(U7-RS)") (class "Default")
      (node (ref "R61") (pin "1") (pinfunction "1_1") (pintype "passive"))
      (node (ref "U7") (pin "8") (pinfunction "RS_8") (pintype "input"))
      (node (ref "U7B") (pin "8") (pinfunction "RS_8") (pintype "bidirectional"))
    )
    (net (code "106") (name "Net-(U8-VOUT)") (class "Default")
      (node (ref "D1") (pin "C") (pinfunction "C_C") (pintype "passive"))
      (node (ref "D3") (pin "C") (pinfunction "C_C") (pintype "passive"))
      (node (ref "L1") (pin "2") (pinfunction "2_2") (pintype "passive"))
      (node (ref "U8") (pin "2") (pinfunction "VOUT_2") (pintype "bidirectional"))
      (node (ref "U8B") (pin "7") (pinfunction "OUT_7") (pintype "passive"))
    )
    (net (code "107") (name "Net-(U10A--IN)") (class "Default")
      (node (ref "R1") (pin "1") (pinfunction "1_1") (pintype "passive"))
      (node (ref "R2") (pin "2") (pinfunction "2_2") (pintype "passive"))
      (node (ref "U10") (pin "13") (pinfunction "-IN_13") (pintype "input"))
      (node (ref "U10") (pin "2") (pinfunction "-IN_2") (pintype "input"))
      (node (ref "U10") (pin "6") (pinfunction "-IN_6") (pintype "input"))
      (node (ref "U10") (pin "9") (pinfunction "-IN_9") (pintype "input"))
      (node (ref "U9") (pin "13") (pinfunction "-IN_13") (pintype "input"))
      (node (ref "U9") (pin "2") (pinfunction "-IN_2") (pintype "input"))
      (node (ref "U9") (pin "6") (pinfunction "-IN_6") (pintype "input"))
      (node (ref "U9") (pin "9") (pinfunction "-IN_9") (pintype "input"))
    )
    (net (code "108") (name "Net-(U10A-OUT)") (class "Default")
      (node (ref "PORTC") (pin "9") (pinfunction "9_9") (pintype "passive"))
      (node (ref "U10") (pin "1") (pinfunction "OUT_1") (pintype "output"))
      (node (ref "U6") (pin "5") (pinfunction "O_5") (pintype "output"))
      (node (ref "X3") (pin "7") (pinfunction "7_7") (pintype "passive"))
    )
    (net (code "109") (name "Net-(U10B-OUT)") (class "Default")
      (node (ref "PORTC") (pin "7") (pinfunction "7_7") (pintype "passive"))
      (node (ref "U10") (pin "7") (pinfunction "OUT_7") (pintype "output"))
      (node (ref "U5") (pin "7") (pinfunction "O_7") (pintype "output"))
      (node (ref "X3") (pin "5") (pinfunction "5_5") (pintype "passive"))
    )
    (net (code "110") (name "Net-(U10C-OUT)") (class "Default")
      (node (ref "PORTC") (pin "8") (pinfunction "8_8") (pintype "passive"))
      (node (ref "U10") (pin "8") (pinfunction "OUT_8") (pintype "output"))
      (node (ref "U5") (pin "5") (pinfunction "O_5") (pintype "output"))
      (node (ref "X3") (pin "6") (pinfunction "6_6") (pintype "passive"))
    )
    (net (code "111") (name "Net-(U10D-OUT)") (class "Default")
      (node (ref "PORTC") (pin "10") (pinfunction "10_10") (pintype "passive"))
      (node (ref "U10") (pin "14") (pinfunction "OUT_14") (pintype "output"))
      (node (ref "U6") (pin "7") (pinfunction "O_7") (pintype "output"))
      (node (ref "X3") (pin "8") (pinfunction "8_8") (pintype "passive"))
    )
    (net (code "112") (name "Net-(U11A-QA)") (class "Default")
      (node (ref "R3") (pin "1") (pinfunction "1_1") (pintype "passive"))
      (node (ref "U11") (pin "15") (pinfunction "QA_15") (pintype "tri_state"))
      (node (ref "U12") (pin "1") (pinfunction "I1_1") (pintype "input"))
    )
    (net (code "113") (name "Net-(U11A-QB)") (class "Default")
      (node (ref "R4") (pin "1") (pinfunction "1_1") (pintype "passive"))
      (node (ref "U11") (pin "1") (pinfunction "QB_1") (pintype "tri_state"))
      (node (ref "U12") (pin "2") (pinfunction "I2_2") (pintype "input"))
    )
    (net (code "114") (name "Net-(U11A-QC)") (class "Default")
      (node (ref "R5") (pin "1") (pinfunction "1_1") (pintype "passive"))
      (node (ref "U11") (pin "2") (pinfunction "QC_2") (pintype "tri_state"))
      (node (ref "U12") (pin "3") (pinfunction "I3_3") (pintype "input"))
    )
    (net (code "115") (name "Net-(U11A-QD)") (class "Default")
      (node (ref "R6") (pin "1") (pinfunction "1_1") (pintype "passive"))
      (node (ref "U11") (pin "3") (pinfunction "QD_3") (pintype "tri_state"))
      (node (ref "U12") (pin "4") (pinfunction "I4_4") (pintype "input"))
    )
    (net (code "116") (name "Net-(U11A-QE)") (class "Default")
      (node (ref "R7") (pin "1") (pinfunction "1_1") (pintype "passive"))
      (node (ref "U11") (pin "4") (pinfunction "QE_4") (pintype "tri_state"))
      (node (ref "U12") (pin "5") (pinfunction "I5_5") (pintype "input"))
    )
    (net (code "117") (name "Net-(U11A-QF)") (class "Default")
      (node (ref "R8") (pin "1") (pinfunction "1_1") (pintype "passive"))
      (node (ref "U11") (pin "5") (pinfunction "QF_5") (pintype "tri_state"))
      (node (ref "U12") (pin "6") (pinfunction "I6_6") (pintype "input"))
    )
    (net (code "118") (name "Net-(U11A-QG)") (class "Default")
      (node (ref "R9") (pin "1") (pinfunction "1_1") (pintype "passive"))
      (node (ref "U11") (pin "6") (pinfunction "QG_6") (pintype "tri_state"))
      (node (ref "U12") (pin "7") (pinfunction "I7_7") (pintype "input"))
    )
    (net (code "119") (name "Net-(U11A-QH)") (class "Default")
      (node (ref "R10") (pin "1") (pinfunction "1_1") (pintype "passive"))
      (node (ref "U11") (pin "7") (pinfunction "QH_7") (pintype "tri_state"))
      (node (ref "U12") (pin "8") (pinfunction "I8_8") (pintype "input"))
    )
    (net (code "120") (name "Net-(U13A-QA)") (class "Default")
      (node (ref "R11") (pin "1") (pinfunction "1_1") (pintype "passive"))
      (node (ref "U13") (pin "15") (pinfunction "QA_15") (pintype "tri_state"))
      (node (ref "U14") (pin "1") (pinfunction "I1_1") (pintype "input"))
    )
    (net (code "121") (name "Net-(U13A-QB)") (class "Default")
      (node (ref "R12") (pin "1") (pinfunction "1_1") (pintype "passive"))
      (node (ref "U13") (pin "1") (pinfunction "QB_1") (pintype "tri_state"))
      (node (ref "U14") (pin "2") (pinfunction "I2_2") (pintype "input"))
    )
    (net (code "122") (name "Net-(U13A-QC)") (class "Default")
      (node (ref "R13") (pin "1") (pinfunction "1_1") (pintype "passive"))
      (node (ref "U13") (pin "2") (pinfunction "QC_2") (pintype "tri_state"))
      (node (ref "U14") (pin "3") (pinfunction "I3_3") (pintype "input"))
    )
    (net (code "123") (name "Net-(U13A-QD)") (class "Default")
      (node (ref "R14") (pin "1") (pinfunction "1_1") (pintype "passive"))
      (node (ref "U13") (pin "3") (pinfunction "QD_3") (pintype "tri_state"))
      (node (ref "U14") (pin "4") (pinfunction "I4_4") (pintype "input"))
    )
    (net (code "124") (name "Net-(U13A-QE)") (class "Default")
      (node (ref "R15") (pin "1") (pinfunction "1_1") (pintype "passive"))
      (node (ref "U13") (pin "4") (pinfunction "QE_4") (pintype "tri_state"))
      (node (ref "U14") (pin "5") (pinfunction "I5_5") (pintype "input"))
    )
    (net (code "125") (name "Net-(U13A-QF)") (class "Default")
      (node (ref "R16") (pin "1") (pinfunction "1_1") (pintype "passive"))
      (node (ref "U13") (pin "5") (pinfunction "QF_5") (pintype "tri_state"))
      (node (ref "U14") (pin "6") (pinfunction "I6_6") (pintype "input"))
    )
    (net (code "126") (name "Net-(U13A-QG)") (class "Default")
      (node (ref "R17") (pin "1") (pinfunction "1_1") (pintype "passive"))
      (node (ref "U13") (pin "6") (pinfunction "QG_6") (pintype "tri_state"))
      (node (ref "U14") (pin "7") (pinfunction "I7_7") (pintype "input"))
    )
    (net (code "127") (name "Net-(U13A-QH)") (class "Default")
      (node (ref "R18") (pin "1") (pinfunction "1_1") (pintype "passive"))
      (node (ref "U13") (pin "7") (pinfunction "QH_7") (pintype "tri_state"))
      (node (ref "U14") (pin "8") (pinfunction "I8_8") (pintype "input"))
    )
    (net (code "128") (name "OLAT") (class "Default")
      (node (ref "R21") (pin "1") (pinfunction "1_1") (pintype "passive"))
      (node (ref "U$1") (pin "PA8") (pinfunction "PA8_PA8") (pintype "bidirectional"))
      (node (ref "U11") (pin "12") (pinfunction "RCK_12") (pintype "input"))
      (node (ref "U13") (pin "12") (pinfunction "RCK_12") (pintype "input"))
    )
    (net (code "129") (name "SCK") (class "Default")
      (node (ref "JP2") (pin "3") (pinfunction "3_3") (pintype "passive"))
      (node (ref "R19") (pin "1") (pinfunction "1_1") (pintype "passive"))
      (node (ref "U$1") (pin "PB3") (pinfunction "PB3_PB3") (pintype "bidirectional"))
      (node (ref "U11") (pin "11") (pinfunction "SCK_11") (pintype "input"))
      (node (ref "U13") (pin "11") (pinfunction "SCK_11") (pintype "input"))
    )
    (net (code "130") (name "SCK2") (class "Default")
      (node (ref "U$1") (pin "PB10") (pinfunction "PB10_PB10") (pintype "bidirectional"))
      (node (ref "U1") (pin "7") (pinfunction "CLK_7") (pintype "input"))
      (node (ref "U2") (pin "7") (pinfunction "CLK_7") (pintype "input"))
    )
    (net (code "131") (name "SLNK1") (class "Default")
      (node (ref "SJ17") (pin "P$1") (pinfunction "1_P$1") (pintype "passive"))
      (node (ref "U11") (pin "9") (pinfunction "QH*_9") (pintype "tri_state"))
      (node (ref "U13") (pin "14") (pinfunction "SER_14") (pintype "input"))
    )
    (net (code "132") (name "SLNK2") (class "Default")
      (node (ref "SJ16") (pin "P$1") (pinfunction "1_P$1") (pintype "passive"))
      (node (ref "U13") (pin "9") (pinfunction "QH*_9") (pintype "tri_state"))
    )
    (net (code "133") (name "SLNK3") (class "Default")
      (node (ref "SJ19") (pin "P$1") (pinfunction "1_P$1") (pintype "passive"))
      (node (ref "U1") (pin "13") (pinfunction "QH_13") (pintype "output"))
      (node (ref "U2") (pin "1") (pinfunction "SER_1") (pintype "input"))
    )
    (net (code "134") (name "SRV1") (class "Default")
      (node (ref "JP5") (pin "2") (pinfunction "2_2") (pintype "passive"))
      (node (ref "R24") (pin "2") (pinfunction "2_2") (pintype "passive"))
      (node (ref "U$1") (pin "PC9") (pinfunction "PC9_PC9") (pintype "bidirectional"))
    )
    (net (code "135") (name "SRV2") (class "Default")
      (node (ref "JP5") (pin "1") (pinfunction "1_1") (pintype "passive"))
      (node (ref "R25") (pin "2") (pinfunction "2_2") (pintype "passive"))
      (node (ref "U$1") (pin "PC7") (pinfunction "PC7_PC7") (pintype "bidirectional"))
    )
    (net (code "136") (name "SRV3") (class "Default")
      (node (ref "JP6") (pin "2") (pinfunction "2_2") (pintype "passive"))
      (node (ref "R26") (pin "2") (pinfunction "2_2") (pintype "passive"))
      (node (ref "U$1") (pin "PC8") (pinfunction "PC8_PC8") (pintype "bidirectional"))
    )
    (net (code "137") (name "SRV4") (class "Default")
      (node (ref "JP6") (pin "1") (pinfunction "1_1") (pintype "passive"))
      (node (ref "R27") (pin "2") (pinfunction "2_2") (pintype "passive"))
      (node (ref "U$1") (pin "PC6") (pinfunction "PC6_PC6") (pintype "bidirectional"))
    )
    (net (code "138") (name "SRV5") (class "Default")
      (node (ref "JP7") (pin "2") (pinfunction "2_2") (pintype "passive"))
      (node (ref "R64") (pin "2") (pinfunction "2_2") (pintype "passive"))
      (node (ref "U$1") (pin "PF1-PH1") (pinfunction "PF1-PH1_PF1-PH1") (pintype "bidirectional"))
    )
    (net (code "139") (name "SRV6") (class "Default")
      (node (ref "JP7") (pin "1") (pinfunction "1_1") (pintype "passive"))
      (node (ref "R65") (pin "2") (pinfunction "2_2") (pintype "passive"))
      (node (ref "U$1") (pin "PA15") (pinfunction "PA15_PA15") (pintype "bidirectional"))
    )
    (net (code "140") (name "SRV7") (class "Default")
      (node (ref "JP8") (pin "2") (pinfunction "2_2") (pintype "passive"))
      (node (ref "R66") (pin "2") (pinfunction "2_2") (pintype "passive"))
      (node (ref "U$1") (pin "PC12") (pinfunction "PC12_PC12") (pintype "bidirectional"))
    )
    (net (code "141") (name "SRV8") (class "Default")
      (node (ref "JP8") (pin "1") (pinfunction "1_1") (pintype "passive"))
      (node (ref "R67") (pin "2") (pinfunction "2_2") (pintype "passive"))
      (node (ref "U$1") (pin "PD2") (pinfunction "PD2_PD2") (pintype "bidirectional"))
    )
    (net (code "142") (name "TDRV1") (class "Default")
      (node (ref "U$1") (pin "PB12") (pinfunction "PB12_PB12") (pintype "bidirectional"))
      (node (ref "U10") (pin "12") (pinfunction "+IN_12") (pintype "input"))
      (node (ref "U6") (pin "2") (pinfunction "I_2") (pintype "input"))
    )
    (net (code "143") (name "TDRV2") (class "Default")
      (node (ref "U$1") (pin "PB2") (pinfunction "PB2_PB2") (pintype "bidirectional"))
      (node (ref "U10") (pin "3") (pinfunction "+IN_3") (pintype "input"))
      (node (ref "U6") (pin "4") (pinfunction "I_4") (pintype "input"))
    )
    (net (code "144") (name "TDRV3") (class "Default")
      (node (ref "U$1") (pin "PB15") (pinfunction "PB15_PB15") (pintype "bidirectional"))
      (node (ref "U10") (pin "10") (pinfunction "+IN_10") (pintype "input"))
      (node (ref "U5") (pin "4") (pinfunction "I_4") (pintype "input"))
    )
    (net (code "145") (name "TDRV4") (class "Default")
      (node (ref "U$1") (pin "PB1") (pinfunction "PB1_PB1") (pintype "bidirectional"))
      (node (ref "U10") (pin "5") (pinfunction "+IN_5") (pintype "input"))
      (node (ref "U5") (pin "2") (pinfunction "I_2") (pintype "input"))
    )
    (net (code "146") (name "TDRV5") (class "Default")
      (node (ref "U$1") (pin "PA0") (pinfunction "PA0_PA0") (pintype "bidirectional"))
      (node (ref "U4") (pin "2") (pinfunction "I_2") (pintype "input"))
      (node (ref "U9") (pin "12") (pinfunction "+IN_12") (pintype "input"))
    )
    (net (code "147") (name "TDRV6") (class "Default")
      (node (ref "U$1") (pin "PA4") (pinfunction "PA4_PA4") (pintype "bidirectional"))
      (node (ref "U4") (pin "4") (pinfunction "I_4") (pintype "input"))
      (node (ref "U9") (pin "3") (pinfunction "+IN_3") (pintype "input"))
    )
    (net (code "148") (name "TDRV7") (class "Default")
      (node (ref "U$1") (pin "PC3") (pinfunction "PC3_PC3") (pintype "bidirectional"))
      (node (ref "U3") (pin "4") (pinfunction "I_4") (pintype "input"))
      (node (ref "U9") (pin "10") (pinfunction "+IN_10") (pintype "input"))
    )
    (net (code "149") (name "TDRV8") (class "Default")
      (node (ref "U$1") (pin "PC0") (pinfunction "PC0_PC0") (pintype "bidirectional"))
      (node (ref "U3") (pin "2") (pinfunction "I_2") (pintype "input"))
      (node (ref "U9") (pin "5") (pinfunction "+IN_5") (pintype "input"))
    )
    (net (code "150") (name "V+") (class "Default")
      (node (ref "C1") (pin "1") (pinfunction "1_1") (pintype "passive"))
      (node (ref "C2") (pin "+") (pinfunction "+_+") (pintype "passive"))
      (node (ref "L1") (pin "1") (pinfunction "1_1") (pintype "passive"))
      (node (ref "U$1") (pin "E5V") (pinfunction "E5V_E5V") (pintype "power_in"))
      (node (ref "U8") (pin "3") (pinfunction "FB_3") (pintype "bidirectional"))
      (node (ref "U8B") (pin "1") (pinfunction "FB_1") (pintype "input"))
    )
    (net (code "151") (name "unconnected-(H1-MOUNT-PadB3,3)") (class "Default")
      (node (ref "H1") (pin "B3,3") (pinfunction "MOUNT_B3,3") (pintype "passive"))
    )
    (net (code "152") (name "unconnected-(H2-MOUNT-PadB3,3)") (class "Default")
      (node (ref "H2") (pin "B3,3") (pinfunction "MOUNT_B3,3") (pintype "passive"))
    )
    (net (code "153") (name "unconnected-(H3-MOUNT-PadB3,3)") (class "Default")
      (node (ref "H3") (pin "B3,3") (pinfunction "MOUNT_B3,3") (pintype "passive"))
    )
    (net (code "154") (name "unconnected-(H4-MOUNT-PadB3,3)") (class "Default")
      (node (ref "H4") (pin "B3,3") (pinfunction "MOUNT_B3,3") (pintype "passive"))
    )
    (net (code "155") (name "unconnected-(J4-Pad1)") (class "Default")
      (node (ref "J4") (pin "1") (pinfunction "1_1") (pintype "passive"))
    )
    (net (code "156") (name "unconnected-(J4-Pad2)") (class "Default")
      (node (ref "J4") (pin "2") (pinfunction "2_2") (pintype "passive"))
    )
    (net (code "157") (name "unconnected-(J4-Pad3)") (class "Default")
      (node (ref "J4") (pin "3") (pinfunction "3_3") (pintype "passive"))
    )
    (net (code "158") (name "unconnected-(U$1-PadBOOT0)") (class "Default")
      (node (ref "U$1") (pin "BOOT0") (pinfunction "BOOT0_BOOT0") (pintype "bidirectional"))
    )
    (net (code "159") (name "unconnected-(U$1-PadIOREF2)") (class "Default")
      (node (ref "U$1") (pin "IOREF2") (pinfunction "IOREF2_IOREF2") (pintype "input"))
    )
    (net (code "160") (name "unconnected-(U$1-PadNC1-PF7)") (class "Default")
      (node (ref "U$1") (pin "NC1-PF7") (pinfunction "NC1-PF7_NC1-PF7") (pintype "bidirectional"))
    )
    (net (code "161") (name "unconnected-(U$1-PadNC2-PF6)") (class "Default")
      (node (ref "U$1") (pin "NC2-PF6") (pinfunction "NC2-PF6_NC2-PF6") (pintype "bidirectional"))
    )
    (net (code "162") (name "unconnected-(U$1-PadNC3)") (class "Default")
      (node (ref "U$1") (pin "NC3") (pinfunction "NC3_NC3") (pintype "no_connect"))
    )
    (net (code "163") (name "unconnected-(U$1-PadNC4)") (class "Default")
      (node (ref "U$1") (pin "NC4") (pinfunction "NC4_NC4") (pintype "no_connect"))
    )
    (net (code "164") (name "unconnected-(U$1-PadNC5-PD8)") (class "Default")
      (node (ref "U$1") (pin "NC5-PD8") (pinfunction "NC5-PD8_NC5-PD8") (pintype "bidirectional"))
    )
    (net (code "165") (name "unconnected-(U$1-PadNC6-PB11)") (class "Default")
      (node (ref "U$1") (pin "NC6-PB11") (pinfunction "NC6-PB11_NC6-PB11") (pintype "no_connect"))
    )
    (net (code "166") (name "unconnected-(U$1-PadNC7-PF5)") (class "Default")
      (node (ref "U$1") (pin "NC7-PF5") (pinfunction "NC7-PF5_NC7-PF5") (pintype "bidirectional"))
    )
    (net (code "167") (name "unconnected-(U$1-PadNC8-PF4)") (class "Default")
      (node (ref "U$1") (pin "NC8-PF4") (pinfunction "NC8-PF4_NC8-PF4") (pintype "bidirectional"))
    )
    (net (code "168") (name "unconnected-(U$1-PadNRESET)") (class "Default")
      (node (ref "U$1") (pin "NRESET") (pinfunction "NRESET_NRESET") (pintype "input"))
    )
    (net (code "169") (name "unconnected-(U$1-PadPA1)") (class "Default")
      (node (ref "U$1") (pin "PA1") (pinfunction "PA1_PA1") (pintype "bidirectional"))
    )
    (net (code "170") (name "unconnected-(U$1-PadPA2)") (class "Default")
      (node (ref "U$1") (pin "PA2") (pinfunction "PA2_PA2") (pintype "bidirectional"))
    )
    (net (code "171") (name "unconnected-(U$1-PadPA3)") (class "Default")
      (node (ref "U$1") (pin "PA3") (pinfunction "PA3_PA3") (pintype "bidirectional"))
    )
    (net (code "172") (name "unconnected-(U$1-PadPA5)") (class "Default")
      (node (ref "U$1") (pin "PA5") (pinfunction "PA5_PA5") (pintype "bidirectional"))
    )
    (net (code "173") (name "unconnected-(U$1-PadPA7)") (class "Default")
      (node (ref "U$1") (pin "PA7") (pinfunction "PA7_PA7") (pintype "bidirectional"))
    )
    (net (code "174") (name "unconnected-(U$1-PadPA9)") (class "Default")
      (node (ref "U$1") (pin "PA9") (pinfunction "PA9_PA9") (pintype "bidirectional"))
    )
    (net (code "175") (name "unconnected-(U$1-PadPA10)") (class "Default")
      (node (ref "U$1") (pin "PA10") (pinfunction "PA10_PA10") (pintype "bidirectional"))
    )
    (net (code "176") (name "unconnected-(U$1-PadPA11)") (class "Default")
      (node (ref "U$1") (pin "PA11") (pinfunction "PA11_PA11") (pintype "bidirectional"))
    )
    (net (code "177") (name "unconnected-(U$1-PadPA12)") (class "Default")
      (node (ref "U$1") (pin "PA12") (pinfunction "PA12_PA12") (pintype "bidirectional"))
    )
    (net (code "178") (name "unconnected-(U$1-PadPA13)") (class "Default")
      (node (ref "U$1") (pin "PA13") (pinfunction "PA13_PA13") (pintype "bidirectional"))
    )
    (net (code "179") (name "unconnected-(U$1-PadPA14)") (class "Default")
      (node (ref "U$1") (pin "PA14") (pinfunction "PA14_PA14") (pintype "bidirectional"))
    )
    (net (code "180") (name "unconnected-(U$1-PadPB0)") (class "Default")
      (node (ref "U$1") (pin "PB0") (pinfunction "PB0_PB0") (pintype "bidirectional"))
    )
    (net (code "181") (name "unconnected-(U$1-PadPB13)") (class "Default")
      (node (ref "U$1") (pin "PB13") (pinfunction "PB13_PB13") (pintype "bidirectional"))
    )
    (net (code "182") (name "unconnected-(U$1-PadPC1)") (class "Default")
      (node (ref "U$1") (pin "PC1") (pinfunction "PC1_PC1") (pintype "bidirectional"))
    )
    (net (code "183") (name "unconnected-(U$1-PadPC4)") (class "Default")
      (node (ref "U$1") (pin "PC4") (pinfunction "PC4_PC4") (pintype "bidirectional"))
    )
    (net (code "184") (name "unconnected-(U$1-PadPC5)") (class "Default")
      (node (ref "U$1") (pin "PC5") (pinfunction "PC5_PC5") (pintype "bidirectional"))
    )
    (net (code "185") (name "unconnected-(U$1-PadPC13)") (class "Default")
      (node (ref "U$1") (pin "PC13") (pinfunction "PC13_PC13") (pintype "bidirectional"))
    )
    (net (code "186") (name "unconnected-(U$1-PadPC14)") (class "Default")
      (node (ref "U$1") (pin "PC14") (pinfunction "PC14_PC14") (pintype "bidirectional"))
    )
    (net (code "187") (name "unconnected-(U$1-PadPC15)") (class "Default")
      (node (ref "U$1") (pin "PC15") (pinfunction "PC15_PC15") (pintype "bidirectional"))
    )
    (net (code "188") (name "unconnected-(U$1-PadPF0-PH0)") (class "Default")
      (node (ref "U$1") (pin "PF0-PH0") (pinfunction "PF0-PH0_PF0-PH0") (pintype "bidirectional"))
    )
  )
)
